# intertubeClock.net
KiCad netlist of a schematic drawn in EAGLE
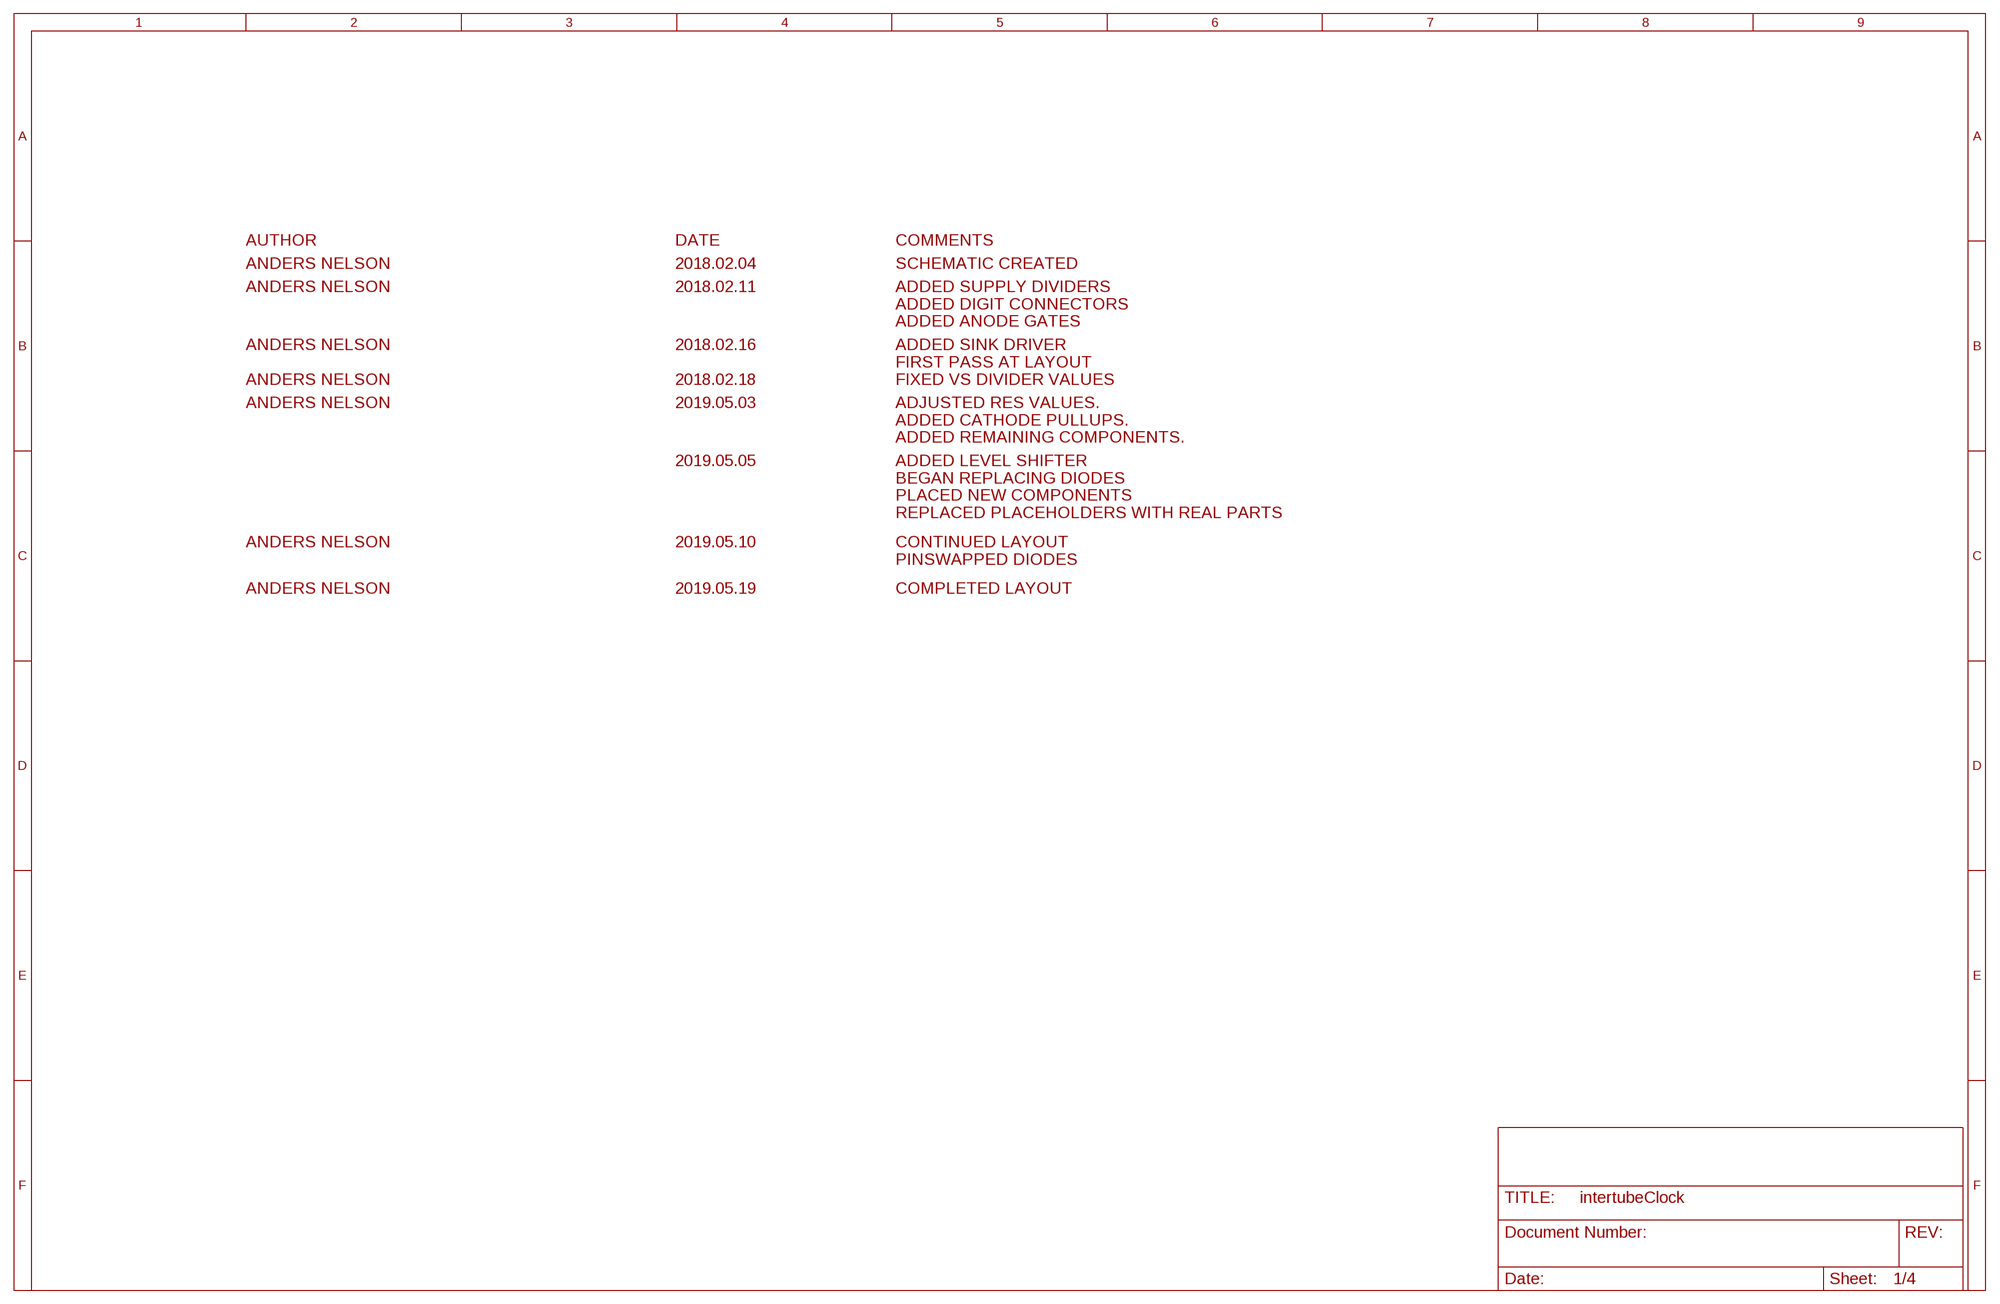
[diagram p0: schematic, sheet 1]
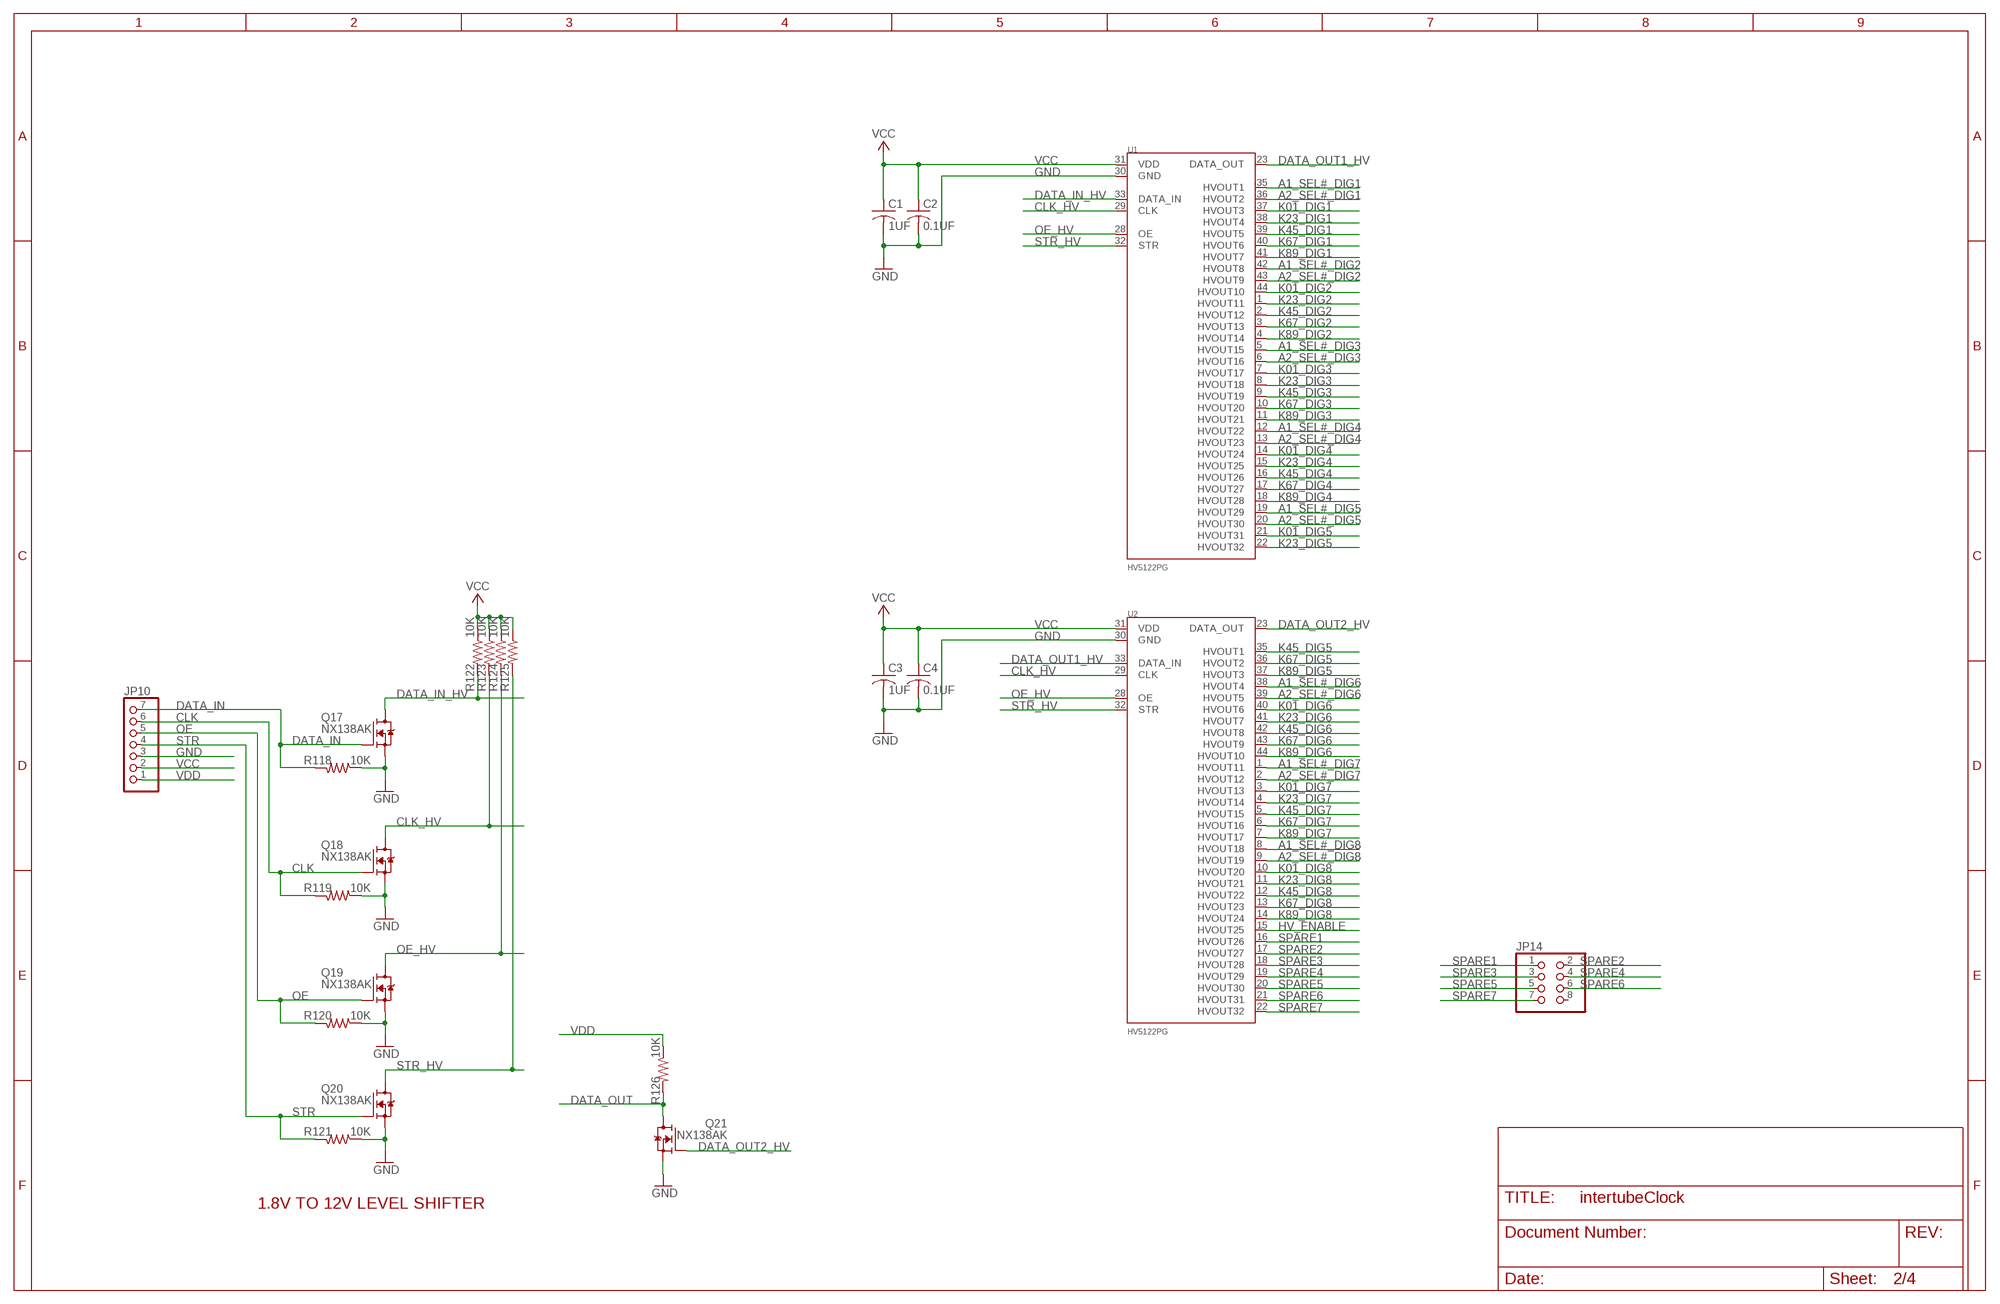
[diagram p1: schematic, sheet 2]
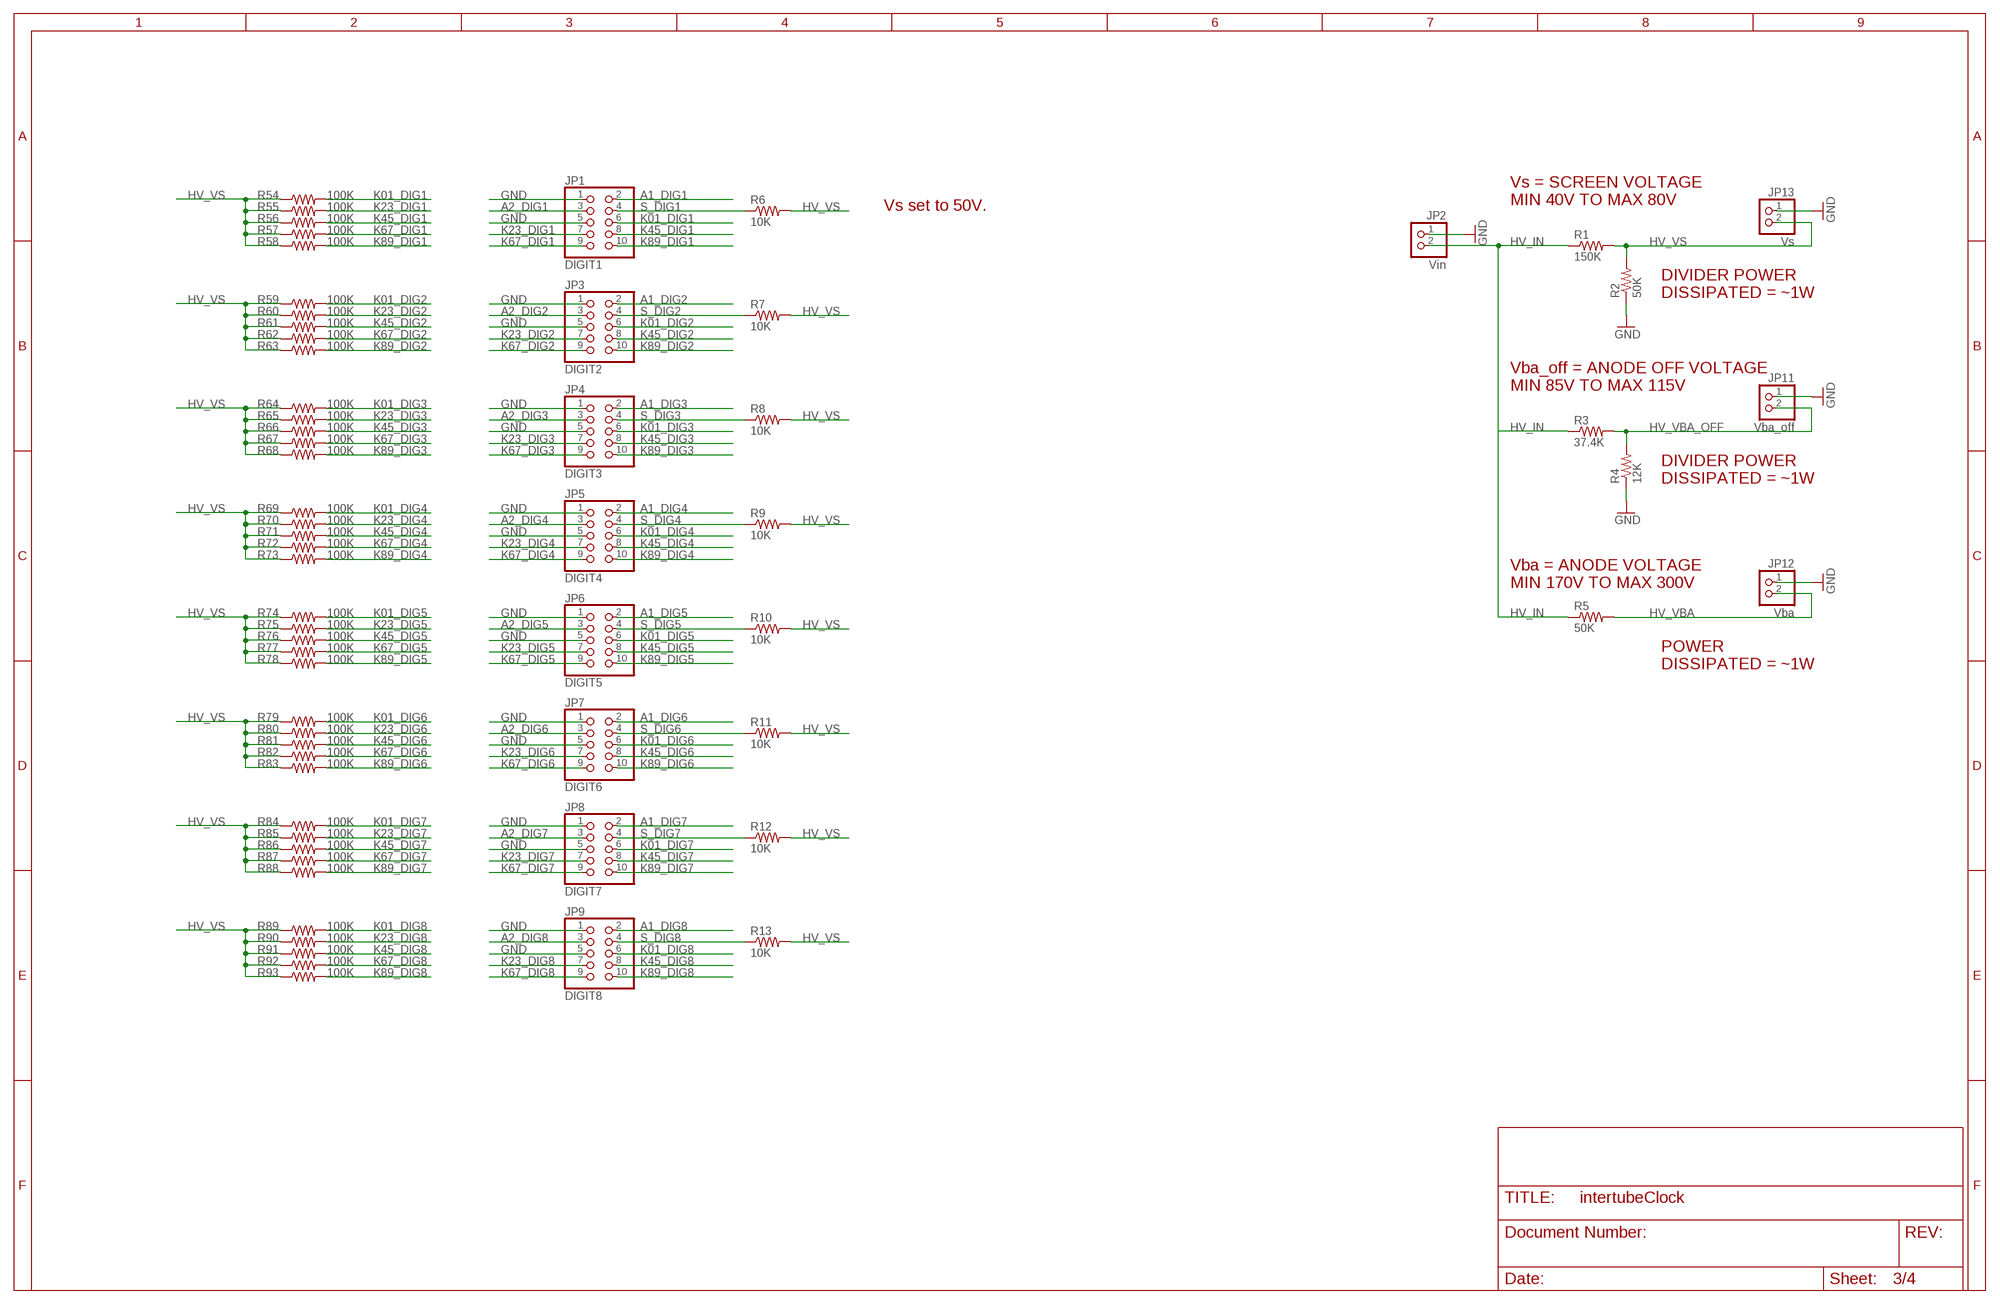
[diagram p2: schematic, sheet 3]
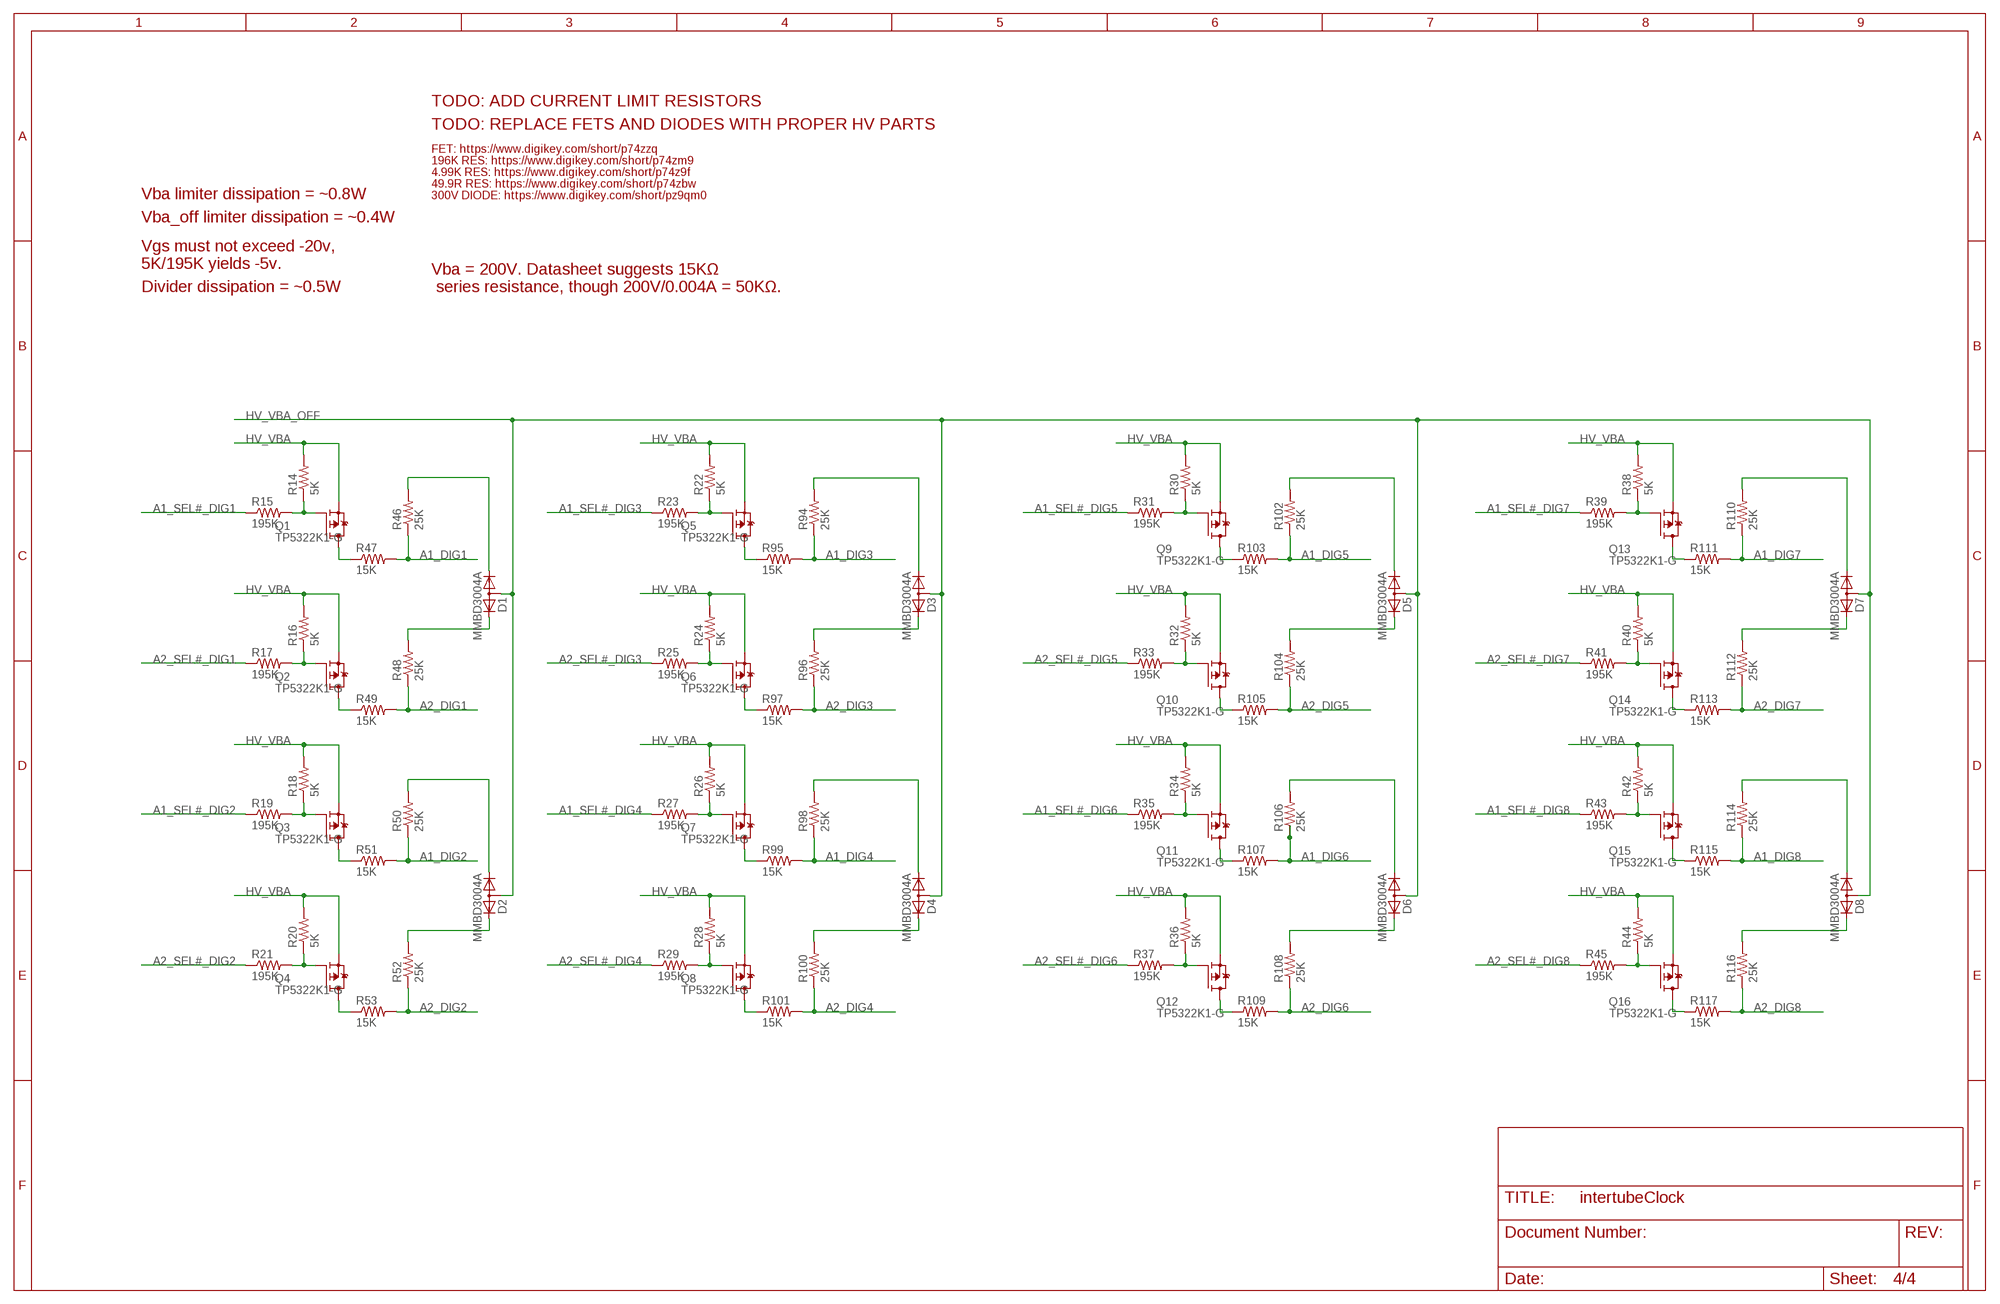
[diagram p3: schematic, sheet 4]

(export (version "E")
  (design (tool "Eeschema 10.0.6"))
  (components
    (comp (ref "JP1")
      (value "DIGIT1")
      (footprint "eagle-import:2X05")
      (libsource (lib "eagle-import") (part "PINHD-2X5"))
    )
    (comp (ref "JP2")
      (value "Vin")
      (footprint "eagle-import:1X02")
      (libsource (lib "eagle-import") (part "PINHD-1X2"))
    )
    (comp (ref "JP3")
      (value "DIGIT2")
      (footprint "eagle-import:2X05")
      (libsource (lib "eagle-import") (part "PINHD-2X5"))
    )
    (comp (ref "JP4")
      (value "DIGIT3")
      (footprint "eagle-import:2X05")
      (libsource (lib "eagle-import") (part "PINHD-2X5"))
    )
    (comp (ref "JP5")
      (value "DIGIT4")
      (footprint "eagle-import:2X05")
      (libsource (lib "eagle-import") (part "PINHD-2X5"))
    )
    (comp (ref "JP6")
      (value "DIGIT5")
      (footprint "eagle-import:2X05")
      (libsource (lib "eagle-import") (part "PINHD-2X5"))
    )
    (comp (ref "JP7")
      (value "DIGIT6")
      (footprint "eagle-import:2X05")
      (libsource (lib "eagle-import") (part "PINHD-2X5"))
    )
    (comp (ref "JP8")
      (value "DIGIT7")
      (footprint "eagle-import:2X05")
      (libsource (lib "eagle-import") (part "PINHD-2X5"))
    )
    (comp (ref "JP9")
      (value "DIGIT8")
      (footprint "eagle-import:2X05")
      (libsource (lib "eagle-import") (part "PINHD-2X5"))
    )
    (comp (ref "JP11")
      (value "Vba_off")
      (footprint "eagle-import:1X02")
      (libsource (lib "eagle-import") (part "PINHD-1X2"))
    )
    (comp (ref "JP12")
      (value "Vba")
      (footprint "eagle-import:1X02")
      (libsource (lib "eagle-import") (part "PINHD-1X2"))
    )
    (comp (ref "JP13")
      (value "Vs")
      (footprint "eagle-import:1X02")
      (libsource (lib "eagle-import") (part "PINHD-1X2"))
    )
    (comp (ref "R1")
      (value "150K")
      (footprint "eagle-import:R2512")
      (libsource (lib "eagle-import") (part "R-US_R2512"))
    )
    (comp (ref "R2")
      (value "50K")
      (footprint "eagle-import:R2512")
      (libsource (lib "eagle-import") (part "R-US_R2512"))
    )
    (comp (ref "R3")
      (value "37.4K")
      (footprint "eagle-import:R2512")
      (libsource (lib "eagle-import") (part "R-US_R2512"))
    )
    (comp (ref "R4")
      (value "12K")
      (footprint "eagle-import:R2512")
      (libsource (lib "eagle-import") (part "R-US_R2512"))
    )
    (comp (ref "R5")
      (value "50K")
      (footprint "eagle-import:R2512")
      (libsource (lib "eagle-import") (part "R-US_R2512"))
    )
    (comp (ref "R6")
      (value "10K")
      (footprint "eagle-import:R1206")
      (libsource (lib "eagle-import") (part "R-US_R1206"))
    )
    (comp (ref "R7")
      (value "10K")
      (footprint "eagle-import:R1206")
      (libsource (lib "eagle-import") (part "R-US_R1206"))
    )
    (comp (ref "R8")
      (value "10K")
      (footprint "eagle-import:R1206")
      (libsource (lib "eagle-import") (part "R-US_R1206"))
    )
    (comp (ref "R9")
      (value "10K")
      (footprint "eagle-import:R1206")
      (libsource (lib "eagle-import") (part "R-US_R1206"))
    )
    (comp (ref "R10")
      (value "10K")
      (footprint "eagle-import:R1206")
      (libsource (lib "eagle-import") (part "R-US_R1206"))
    )
    (comp (ref "R11")
      (value "10K")
      (footprint "eagle-import:R1206")
      (libsource (lib "eagle-import") (part "R-US_R1206"))
    )
    (comp (ref "R12")
      (value "10K")
      (footprint "eagle-import:R1206")
      (libsource (lib "eagle-import") (part "R-US_R1206"))
    )
    (comp (ref "R13")
      (value "10K")
      (footprint "eagle-import:R1206")
      (libsource (lib "eagle-import") (part "R-US_R1206"))
    )
    (comp (ref "R54")
      (value "100K")
      (footprint "eagle-import:R1206")
      (libsource (lib "eagle-import") (part "R-US_R1206"))
    )
    (comp (ref "R55")
      (value "100K")
      (footprint "eagle-import:R1206")
      (libsource (lib "eagle-import") (part "R-US_R1206"))
    )
    (comp (ref "R56")
      (value "100K")
      (footprint "eagle-import:R1206")
      (libsource (lib "eagle-import") (part "R-US_R1206"))
    )
    (comp (ref "R57")
      (value "100K")
      (footprint "eagle-import:R1206")
      (libsource (lib "eagle-import") (part "R-US_R1206"))
    )
    (comp (ref "R58")
      (value "100K")
      (footprint "eagle-import:R1206")
      (libsource (lib "eagle-import") (part "R-US_R1206"))
    )
    (comp (ref "R59")
      (value "100K")
      (footprint "eagle-import:R1206")
      (libsource (lib "eagle-import") (part "R-US_R1206"))
    )
    (comp (ref "R60")
      (value "100K")
      (footprint "eagle-import:R1206")
      (libsource (lib "eagle-import") (part "R-US_R1206"))
    )
    (comp (ref "R61")
      (value "100K")
      (footprint "eagle-import:R1206")
      (libsource (lib "eagle-import") (part "R-US_R1206"))
    )
    (comp (ref "R62")
      (value "100K")
      (footprint "eagle-import:R1206")
      (libsource (lib "eagle-import") (part "R-US_R1206"))
    )
    (comp (ref "R63")
      (value "100K")
      (footprint "eagle-import:R1206")
      (libsource (lib "eagle-import") (part "R-US_R1206"))
    )
    (comp (ref "R64")
      (value "100K")
      (footprint "eagle-import:R1206")
      (libsource (lib "eagle-import") (part "R-US_R1206"))
    )
    (comp (ref "R65")
      (value "100K")
      (footprint "eagle-import:R1206")
      (libsource (lib "eagle-import") (part "R-US_R1206"))
    )
    (comp (ref "R66")
      (value "100K")
      (footprint "eagle-import:R1206")
      (libsource (lib "eagle-import") (part "R-US_R1206"))
    )
    (comp (ref "R67")
      (value "100K")
      (footprint "eagle-import:R1206")
      (libsource (lib "eagle-import") (part "R-US_R1206"))
    )
    (comp (ref "R68")
      (value "100K")
      (footprint "eagle-import:R1206")
      (libsource (lib "eagle-import") (part "R-US_R1206"))
    )
    (comp (ref "R69")
      (value "100K")
      (footprint "eagle-import:R1206")
      (libsource (lib "eagle-import") (part "R-US_R1206"))
    )
    (comp (ref "R70")
      (value "100K")
      (footprint "eagle-import:R1206")
      (libsource (lib "eagle-import") (part "R-US_R1206"))
    )
    (comp (ref "R71")
      (value "100K")
      (footprint "eagle-import:R1206")
      (libsource (lib "eagle-import") (part "R-US_R1206"))
    )
    (comp (ref "R72")
      (value "100K")
      (footprint "eagle-import:R1206")
      (libsource (lib "eagle-import") (part "R-US_R1206"))
    )
    (comp (ref "R73")
      (value "100K")
      (footprint "eagle-import:R1206")
      (libsource (lib "eagle-import") (part "R-US_R1206"))
    )
    (comp (ref "R74")
      (value "100K")
      (footprint "eagle-import:R1206")
      (libsource (lib "eagle-import") (part "R-US_R1206"))
    )
    (comp (ref "R75")
      (value "100K")
      (footprint "eagle-import:R1206")
      (libsource (lib "eagle-import") (part "R-US_R1206"))
    )
    (comp (ref "R76")
      (value "100K")
      (footprint "eagle-import:R1206")
      (libsource (lib "eagle-import") (part "R-US_R1206"))
    )
    (comp (ref "R77")
      (value "100K")
      (footprint "eagle-import:R1206")
      (libsource (lib "eagle-import") (part "R-US_R1206"))
    )
    (comp (ref "R78")
      (value "100K")
      (footprint "eagle-import:R1206")
      (libsource (lib "eagle-import") (part "R-US_R1206"))
    )
    (comp (ref "R79")
      (value "100K")
      (footprint "eagle-import:R1206")
      (libsource (lib "eagle-import") (part "R-US_R1206"))
    )
    (comp (ref "R80")
      (value "100K")
      (footprint "eagle-import:R1206")
      (libsource (lib "eagle-import") (part "R-US_R1206"))
    )
    (comp (ref "R81")
      (value "100K")
      (footprint "eagle-import:R1206")
      (libsource (lib "eagle-import") (part "R-US_R1206"))
    )
    (comp (ref "R82")
      (value "100K")
      (footprint "eagle-import:R1206")
      (libsource (lib "eagle-import") (part "R-US_R1206"))
    )
    (comp (ref "R83")
      (value "100K")
      (footprint "eagle-import:R1206")
      (libsource (lib "eagle-import") (part "R-US_R1206"))
    )
    (comp (ref "R84")
      (value "100K")
      (footprint "eagle-import:R1206")
      (libsource (lib "eagle-import") (part "R-US_R1206"))
    )
    (comp (ref "R85")
      (value "100K")
      (footprint "eagle-import:R1206")
      (libsource (lib "eagle-import") (part "R-US_R1206"))
    )
    (comp (ref "R86")
      (value "100K")
      (footprint "eagle-import:R1206")
      (libsource (lib "eagle-import") (part "R-US_R1206"))
    )
    (comp (ref "R87")
      (value "100K")
      (footprint "eagle-import:R1206")
      (libsource (lib "eagle-import") (part "R-US_R1206"))
    )
    (comp (ref "R88")
      (value "100K")
      (footprint "eagle-import:R1206")
      (libsource (lib "eagle-import") (part "R-US_R1206"))
    )
    (comp (ref "R89")
      (value "100K")
      (footprint "eagle-import:R1206")
      (libsource (lib "eagle-import") (part "R-US_R1206"))
    )
    (comp (ref "R90")
      (value "100K")
      (footprint "eagle-import:R1206")
      (libsource (lib "eagle-import") (part "R-US_R1206"))
    )
    (comp (ref "R91")
      (value "100K")
      (footprint "eagle-import:R1206")
      (libsource (lib "eagle-import") (part "R-US_R1206"))
    )
    (comp (ref "R92")
      (value "100K")
      (footprint "eagle-import:R1206")
      (libsource (lib "eagle-import") (part "R-US_R1206"))
    )
    (comp (ref "R93")
      (value "100K")
      (footprint "eagle-import:R1206")
      (libsource (lib "eagle-import") (part "R-US_R1206"))
    )
    (comp (ref "D1")
      (value "MMBD3004A")
      (footprint "eagle-import:SOT23")
      (libsource (lib "eagle-import") (part "MMBD3004A"))
    )
    (comp (ref "D2")
      (value "MMBD3004A")
      (footprint "eagle-import:SOT23")
      (libsource (lib "eagle-import") (part "MMBD3004A"))
    )
    (comp (ref "D3")
      (value "MMBD3004A")
      (footprint "eagle-import:SOT23")
      (libsource (lib "eagle-import") (part "MMBD3004A"))
    )
    (comp (ref "D4")
      (value "MMBD3004A")
      (footprint "eagle-import:SOT23")
      (libsource (lib "eagle-import") (part "MMBD3004A"))
    )
    (comp (ref "D5")
      (value "MMBD3004A")
      (footprint "eagle-import:SOT23")
      (libsource (lib "eagle-import") (part "MMBD3004A"))
    )
    (comp (ref "D6")
      (value "MMBD3004A")
      (footprint "eagle-import:SOT23")
      (libsource (lib "eagle-import") (part "MMBD3004A"))
    )
    (comp (ref "D7")
      (value "MMBD3004A")
      (footprint "eagle-import:SOT23")
      (libsource (lib "eagle-import") (part "MMBD3004A"))
    )
    (comp (ref "D8")
      (value "MMBD3004A")
      (footprint "eagle-import:SOT23")
      (libsource (lib "eagle-import") (part "MMBD3004A"))
    )
    (comp (ref "Q1")
      (value "TP5322K1-G")
      (footprint "eagle-import:SOT23")
      (libsource (lib "eagle-import") (part "TP5322K1-G"))
    )
    (comp (ref "Q2")
      (value "TP5322K1-G")
      (footprint "eagle-import:SOT23")
      (libsource (lib "eagle-import") (part "TP5322K1-G"))
    )
    (comp (ref "Q3")
      (value "TP5322K1-G")
      (footprint "eagle-import:SOT23")
      (libsource (lib "eagle-import") (part "TP5322K1-G"))
    )
    (comp (ref "Q4")
      (value "TP5322K1-G")
      (footprint "eagle-import:SOT23")
      (libsource (lib "eagle-import") (part "TP5322K1-G"))
    )
    (comp (ref "Q5")
      (value "TP5322K1-G")
      (footprint "eagle-import:SOT23")
      (libsource (lib "eagle-import") (part "TP5322K1-G"))
    )
    (comp (ref "Q6")
      (value "TP5322K1-G")
      (footprint "eagle-import:SOT23")
      (libsource (lib "eagle-import") (part "TP5322K1-G"))
    )
    (comp (ref "Q7")
      (value "TP5322K1-G")
      (footprint "eagle-import:SOT23")
      (libsource (lib "eagle-import") (part "TP5322K1-G"))
    )
    (comp (ref "Q8")
      (value "TP5322K1-G")
      (footprint "eagle-import:SOT23")
      (libsource (lib "eagle-import") (part "TP5322K1-G"))
    )
    (comp (ref "Q9")
      (value "TP5322K1-G")
      (footprint "eagle-import:SOT23")
      (libsource (lib "eagle-import") (part "TP5322K1-G"))
    )
    (comp (ref "Q10")
      (value "TP5322K1-G")
      (footprint "eagle-import:SOT23")
      (libsource (lib "eagle-import") (part "TP5322K1-G"))
    )
    (comp (ref "Q11")
      (value "TP5322K1-G")
      (footprint "eagle-import:SOT23")
      (libsource (lib "eagle-import") (part "TP5322K1-G"))
    )
    (comp (ref "Q12")
      (value "TP5322K1-G")
      (footprint "eagle-import:SOT23")
      (libsource (lib "eagle-import") (part "TP5322K1-G"))
    )
    (comp (ref "Q13")
      (value "TP5322K1-G")
      (footprint "eagle-import:SOT23")
      (libsource (lib "eagle-import") (part "TP5322K1-G"))
    )
    (comp (ref "Q14")
      (value "TP5322K1-G")
      (footprint "eagle-import:SOT23")
      (libsource (lib "eagle-import") (part "TP5322K1-G"))
    )
    (comp (ref "Q15")
      (value "TP5322K1-G")
      (footprint "eagle-import:SOT23")
      (libsource (lib "eagle-import") (part "TP5322K1-G"))
    )
    (comp (ref "Q16")
      (value "TP5322K1-G")
      (footprint "eagle-import:SOT23")
      (libsource (lib "eagle-import") (part "TP5322K1-G"))
    )
    (comp (ref "R14")
      (value "5K")
      (footprint "eagle-import:R1206")
      (libsource (lib "eagle-import") (part "R-US_R1206"))
    )
    (comp (ref "R15")
      (value "195K")
      (footprint "eagle-import:R1206")
      (libsource (lib "eagle-import") (part "R-US_R1206"))
    )
    (comp (ref "R16")
      (value "5K")
      (footprint "eagle-import:R1206")
      (libsource (lib "eagle-import") (part "R-US_R1206"))
    )
    (comp (ref "R17")
      (value "195K")
      (footprint "eagle-import:R1206")
      (libsource (lib "eagle-import") (part "R-US_R1206"))
    )
    (comp (ref "R18")
      (value "5K")
      (footprint "eagle-import:R1206")
      (libsource (lib "eagle-import") (part "R-US_R1206"))
    )
    (comp (ref "R19")
      (value "195K")
      (footprint "eagle-import:R1206")
      (libsource (lib "eagle-import") (part "R-US_R1206"))
    )
    (comp (ref "R20")
      (value "5K")
      (footprint "eagle-import:R1206")
      (libsource (lib "eagle-import") (part "R-US_R1206"))
    )
    (comp (ref "R21")
      (value "195K")
      (footprint "eagle-import:R1206")
      (libsource (lib "eagle-import") (part "R-US_R1206"))
    )
    (comp (ref "R22")
      (value "5K")
      (footprint "eagle-import:R1206")
      (libsource (lib "eagle-import") (part "R-US_R1206"))
    )
    (comp (ref "R23")
      (value "195K")
      (footprint "eagle-import:R1206")
      (libsource (lib "eagle-import") (part "R-US_R1206"))
    )
    (comp (ref "R24")
      (value "5K")
      (footprint "eagle-import:R1206")
      (libsource (lib "eagle-import") (part "R-US_R1206"))
    )
    (comp (ref "R25")
      (value "195K")
      (footprint "eagle-import:R1206")
      (libsource (lib "eagle-import") (part "R-US_R1206"))
    )
    (comp (ref "R26")
      (value "5K")
      (footprint "eagle-import:R1206")
      (libsource (lib "eagle-import") (part "R-US_R1206"))
    )
    (comp (ref "R27")
      (value "195K")
      (footprint "eagle-import:R1206")
      (libsource (lib "eagle-import") (part "R-US_R1206"))
    )
    (comp (ref "R28")
      (value "5K")
      (footprint "eagle-import:R1206")
      (libsource (lib "eagle-import") (part "R-US_R1206"))
    )
    (comp (ref "R29")
      (value "195K")
      (footprint "eagle-import:R1206")
      (libsource (lib "eagle-import") (part "R-US_R1206"))
    )
    (comp (ref "R30")
      (value "5K")
      (footprint "eagle-import:R1206")
      (libsource (lib "eagle-import") (part "R-US_R1206"))
    )
    (comp (ref "R31")
      (value "195K")
      (footprint "eagle-import:R1206")
      (libsource (lib "eagle-import") (part "R-US_R1206"))
    )
    (comp (ref "R32")
      (value "5K")
      (footprint "eagle-import:R1206")
      (libsource (lib "eagle-import") (part "R-US_R1206"))
    )
    (comp (ref "R33")
      (value "195K")
      (footprint "eagle-import:R1206")
      (libsource (lib "eagle-import") (part "R-US_R1206"))
    )
    (comp (ref "R34")
      (value "5K")
      (footprint "eagle-import:R1206")
      (libsource (lib "eagle-import") (part "R-US_R1206"))
    )
    (comp (ref "R35")
      (value "195K")
      (footprint "eagle-import:R1206")
      (libsource (lib "eagle-import") (part "R-US_R1206"))
    )
    (comp (ref "R36")
      (value "5K")
      (footprint "eagle-import:R1206")
      (libsource (lib "eagle-import") (part "R-US_R1206"))
    )
    (comp (ref "R37")
      (value "195K")
      (footprint "eagle-import:R1206")
      (libsource (lib "eagle-import") (part "R-US_R1206"))
    )
    (comp (ref "R38")
      (value "5K")
      (footprint "eagle-import:R1206")
      (libsource (lib "eagle-import") (part "R-US_R1206"))
    )
    (comp (ref "R39")
      (value "195K")
      (footprint "eagle-import:R1206")
      (libsource (lib "eagle-import") (part "R-US_R1206"))
    )
    (comp (ref "R40")
      (value "5K")
      (footprint "eagle-import:R1206")
      (libsource (lib "eagle-import") (part "R-US_R1206"))
    )
    (comp (ref "R41")
      (value "195K")
      (footprint "eagle-import:R1206")
      (libsource (lib "eagle-import") (part "R-US_R1206"))
    )
    (comp (ref "R42")
      (value "5K")
      (footprint "eagle-import:R1206")
      (libsource (lib "eagle-import") (part "R-US_R1206"))
    )
    (comp (ref "R43")
      (value "195K")
      (footprint "eagle-import:R1206")
      (libsource (lib "eagle-import") (part "R-US_R1206"))
    )
    (comp (ref "R44")
      (value "5K")
      (footprint "eagle-import:R1206")
      (libsource (lib "eagle-import") (part "R-US_R1206"))
    )
    (comp (ref "R45")
      (value "195K")
      (footprint "eagle-import:R1206")
      (libsource (lib "eagle-import") (part "R-US_R1206"))
    )
    (comp (ref "R46")
      (value "25K")
      (footprint "eagle-import:R1206")
      (libsource (lib "eagle-import") (part "R-US_R1206"))
    )
    (comp (ref "R47")
      (value "15K")
      (footprint "eagle-import:R1206")
      (libsource (lib "eagle-import") (part "R-US_R1206"))
    )
    (comp (ref "R48")
      (value "25K")
      (footprint "eagle-import:R1206")
      (libsource (lib "eagle-import") (part "R-US_R1206"))
    )
    (comp (ref "R49")
      (value "15K")
      (footprint "eagle-import:R1206")
      (libsource (lib "eagle-import") (part "R-US_R1206"))
    )
    (comp (ref "R50")
      (value "25K")
      (footprint "eagle-import:R1206")
      (libsource (lib "eagle-import") (part "R-US_R1206"))
    )
    (comp (ref "R51")
      (value "15K")
      (footprint "eagle-import:R1206")
      (libsource (lib "eagle-import") (part "R-US_R1206"))
    )
    (comp (ref "R52")
      (value "25K")
      (footprint "eagle-import:R1206")
      (libsource (lib "eagle-import") (part "R-US_R1206"))
    )
    (comp (ref "R53")
      (value "15K")
      (footprint "eagle-import:R1206")
      (libsource (lib "eagle-import") (part "R-US_R1206"))
    )
    (comp (ref "R94")
      (value "25K")
      (footprint "eagle-import:R1206")
      (libsource (lib "eagle-import") (part "R-US_R1206"))
    )
    (comp (ref "R95")
      (value "15K")
      (footprint "eagle-import:R1206")
      (libsource (lib "eagle-import") (part "R-US_R1206"))
    )
    (comp (ref "R96")
      (value "25K")
      (footprint "eagle-import:R1206")
      (libsource (lib "eagle-import") (part "R-US_R1206"))
    )
    (comp (ref "R97")
      (value "15K")
      (footprint "eagle-import:R1206")
      (libsource (lib "eagle-import") (part "R-US_R1206"))
    )
    (comp (ref "R98")
      (value "25K")
      (footprint "eagle-import:R1206")
      (libsource (lib "eagle-import") (part "R-US_R1206"))
    )
    (comp (ref "R99")
      (value "15K")
      (footprint "eagle-import:R1206")
      (libsource (lib "eagle-import") (part "R-US_R1206"))
    )
    (comp (ref "R100")
      (value "25K")
      (footprint "eagle-import:R1206")
      (libsource (lib "eagle-import") (part "R-US_R1206"))
    )
    (comp (ref "R101")
      (value "15K")
      (footprint "eagle-import:R1206")
      (libsource (lib "eagle-import") (part "R-US_R1206"))
    )
    (comp (ref "R102")
      (value "25K")
      (footprint "eagle-import:R1206")
      (libsource (lib "eagle-import") (part "R-US_R1206"))
    )
    (comp (ref "R103")
      (value "15K")
      (footprint "eagle-import:R1206")
      (libsource (lib "eagle-import") (part "R-US_R1206"))
    )
    (comp (ref "R104")
      (value "25K")
      (footprint "eagle-import:R1206")
      (libsource (lib "eagle-import") (part "R-US_R1206"))
    )
    (comp (ref "R105")
      (value "15K")
      (footprint "eagle-import:R1206")
      (libsource (lib "eagle-import") (part "R-US_R1206"))
    )
    (comp (ref "R106")
      (value "25K")
      (footprint "eagle-import:R1206")
      (libsource (lib "eagle-import") (part "R-US_R1206"))
    )
    (comp (ref "R107")
      (value "15K")
      (footprint "eagle-import:R1206")
      (libsource (lib "eagle-import") (part "R-US_R1206"))
    )
    (comp (ref "R108")
      (value "25K")
      (footprint "eagle-import:R1206")
      (libsource (lib "eagle-import") (part "R-US_R1206"))
    )
    (comp (ref "R109")
      (value "15K")
      (footprint "eagle-import:R1206")
      (libsource (lib "eagle-import") (part "R-US_R1206"))
    )
    (comp (ref "R110")
      (value "25K")
      (footprint "eagle-import:R1206")
      (libsource (lib "eagle-import") (part "R-US_R1206"))
    )
    (comp (ref "R111")
      (value "15K")
      (footprint "eagle-import:R1206")
      (libsource (lib "eagle-import") (part "R-US_R1206"))
    )
    (comp (ref "R112")
      (value "25K")
      (footprint "eagle-import:R1206")
      (libsource (lib "eagle-import") (part "R-US_R1206"))
    )
    (comp (ref "R113")
      (value "15K")
      (footprint "eagle-import:R1206")
      (libsource (lib "eagle-import") (part "R-US_R1206"))
    )
    (comp (ref "R114")
      (value "25K")
      (footprint "eagle-import:R1206")
      (libsource (lib "eagle-import") (part "R-US_R1206"))
    )
    (comp (ref "R115")
      (value "15K")
      (footprint "eagle-import:R1206")
      (libsource (lib "eagle-import") (part "R-US_R1206"))
    )
    (comp (ref "R116")
      (value "25K")
      (footprint "eagle-import:R1206")
      (libsource (lib "eagle-import") (part "R-US_R1206"))
    )
    (comp (ref "R117")
      (value "15K")
      (footprint "eagle-import:R1206")
      (libsource (lib "eagle-import") (part "R-US_R1206"))
    )
    (comp (ref "C1")
      (value "1UF")
      (footprint "eagle-import:C0805")
      (libsource (lib "eagle-import") (part "C-USC0805"))
    )
    (comp (ref "C2")
      (value "0.1UF")
      (footprint "eagle-import:C0805")
      (libsource (lib "eagle-import") (part "C-USC0805"))
    )
    (comp (ref "C3")
      (value "1UF")
      (footprint "eagle-import:C0805")
      (libsource (lib "eagle-import") (part "C-USC0805"))
    )
    (comp (ref "C4")
      (value "0.1UF")
      (footprint "eagle-import:C0805")
      (libsource (lib "eagle-import") (part "C-USC0805"))
    )
    (comp (ref "JP10")
      (value "PINHD-1X7")
      (footprint "eagle-import:1X07")
      (libsource (lib "eagle-import") (part "PINHD-1X7"))
    )
    (comp (ref "JP14")
      (value "PINHD-2X4")
      (footprint "eagle-import:2X04")
      (libsource (lib "eagle-import") (part "PINHD-2X4"))
    )
    (comp (ref "Q17")
      (value "NX138AK")
      (footprint "eagle-import:SOT23")
      (libsource (lib "eagle-import") (part "NX138AK"))
    )
    (comp (ref "Q18")
      (value "NX138AK")
      (footprint "eagle-import:SOT23")
      (libsource (lib "eagle-import") (part "NX138AK"))
    )
    (comp (ref "Q19")
      (value "NX138AK")
      (footprint "eagle-import:SOT23")
      (libsource (lib "eagle-import") (part "NX138AK"))
    )
    (comp (ref "Q20")
      (value "NX138AK")
      (footprint "eagle-import:SOT23")
      (libsource (lib "eagle-import") (part "NX138AK"))
    )
    (comp (ref "Q21")
      (value "NX138AK")
      (footprint "eagle-import:SOT23")
      (libsource (lib "eagle-import") (part "NX138AK"))
    )
    (comp (ref "R118")
      (value "10K")
      (footprint "eagle-import:R0603")
      (libsource (lib "eagle-import") (part "R-US_R0603"))
    )
    (comp (ref "R119")
      (value "10K")
      (footprint "eagle-import:R0603")
      (libsource (lib "eagle-import") (part "R-US_R0603"))
    )
    (comp (ref "R120")
      (value "10K")
      (footprint "eagle-import:R0603")
      (libsource (lib "eagle-import") (part "R-US_R0603"))
    )
    (comp (ref "R121")
      (value "10K")
      (footprint "eagle-import:R0603")
      (libsource (lib "eagle-import") (part "R-US_R0603"))
    )
    (comp (ref "R122")
      (value "10K")
      (footprint "eagle-import:R0603")
      (libsource (lib "eagle-import") (part "R-US_R0603"))
    )
    (comp (ref "R123")
      (value "10K")
      (footprint "eagle-import:R0603")
      (libsource (lib "eagle-import") (part "R-US_R0603"))
    )
    (comp (ref "R124")
      (value "10K")
      (footprint "eagle-import:R0603")
      (libsource (lib "eagle-import") (part "R-US_R0603"))
    )
    (comp (ref "R125")
      (value "10K")
      (footprint "eagle-import:R0603")
      (libsource (lib "eagle-import") (part "R-US_R0603"))
    )
    (comp (ref "R126")
      (value "10K")
      (footprint "eagle-import:R0603")
      (libsource (lib "eagle-import") (part "R-US_R0603"))
    )
    (comp (ref "U1")
      (value "HV5122PG")
      (footprint "eagle-import:TQFP44")
      (libsource (lib "eagle-import") (part "HV5PG122"))
    )
    (comp (ref "U2")
      (value "HV5122PG")
      (footprint "eagle-import:TQFP44")
      (libsource (lib "eagle-import") (part "HV5PG122"))
    )
  )
  (nets
    (net (code "1") (name "A1_DIG1") (class "Default")
      (node (ref "JP1") (pin "2") (pinfunction "2_2") (pintype "passive"))
      (node (ref "R46") (pin "1") (pinfunction "1_1") (pintype "passive"))
      (node (ref "R47") (pin "2") (pinfunction "2_2") (pintype "passive"))
    )
    (net (code "2") (name "A1_DIG2") (class "Default")
      (node (ref "JP3") (pin "2") (pinfunction "2_2") (pintype "passive"))
      (node (ref "R50") (pin "1") (pinfunction "1_1") (pintype "passive"))
      (node (ref "R51") (pin "2") (pinfunction "2_2") (pintype "passive"))
    )
    (net (code "3") (name "A1_DIG3") (class "Default")
      (node (ref "JP4") (pin "2") (pinfunction "2_2") (pintype "passive"))
      (node (ref "R94") (pin "1") (pinfunction "1_1") (pintype "passive"))
      (node (ref "R95") (pin "2") (pinfunction "2_2") (pintype "passive"))
    )
    (net (code "4") (name "A1_DIG4") (class "Default")
      (node (ref "JP5") (pin "2") (pinfunction "2_2") (pintype "passive"))
      (node (ref "R98") (pin "1") (pinfunction "1_1") (pintype "passive"))
      (node (ref "R99") (pin "2") (pinfunction "2_2") (pintype "passive"))
    )
    (net (code "5") (name "A1_DIG5") (class "Default")
      (node (ref "JP6") (pin "2") (pinfunction "2_2") (pintype "passive"))
      (node (ref "R102") (pin "1") (pinfunction "1_1") (pintype "passive"))
      (node (ref "R103") (pin "2") (pinfunction "2_2") (pintype "passive"))
    )
    (net (code "6") (name "A1_DIG6") (class "Default")
      (node (ref "JP7") (pin "2") (pinfunction "2_2") (pintype "passive"))
      (node (ref "R106") (pin "1") (pinfunction "1_1") (pintype "passive"))
      (node (ref "R107") (pin "2") (pinfunction "2_2") (pintype "passive"))
    )
    (net (code "7") (name "A1_DIG7") (class "Default")
      (node (ref "JP8") (pin "2") (pinfunction "2_2") (pintype "passive"))
      (node (ref "R110") (pin "1") (pinfunction "1_1") (pintype "passive"))
      (node (ref "R111") (pin "2") (pinfunction "2_2") (pintype "passive"))
    )
    (net (code "8") (name "A1_DIG8") (class "Default")
      (node (ref "JP9") (pin "2") (pinfunction "2_2") (pintype "passive"))
      (node (ref "R114") (pin "1") (pinfunction "1_1") (pintype "passive"))
      (node (ref "R115") (pin "2") (pinfunction "2_2") (pintype "passive"))
    )
    (net (code "9") (name "A1_SEL#_DIG1") (class "Default")
      (node (ref "R15") (pin "1") (pinfunction "1_1") (pintype "passive"))
      (node (ref "U1") (pin "35") (pinfunction "HVOUT1_35") (pintype "bidirectional"))
    )
    (net (code "10") (name "A1_SEL#_DIG2") (class "Default")
      (node (ref "R19") (pin "1") (pinfunction "1_1") (pintype "passive"))
      (node (ref "U1") (pin "42") (pinfunction "HVOUT8_42") (pintype "bidirectional"))
    )
    (net (code "11") (name "A1_SEL#_DIG3") (class "Default")
      (node (ref "R23") (pin "1") (pinfunction "1_1") (pintype "passive"))
      (node (ref "U1") (pin "5") (pinfunction "HVOUT15_5") (pintype "bidirectional"))
    )
    (net (code "12") (name "A1_SEL#_DIG4") (class "Default")
      (node (ref "R27") (pin "1") (pinfunction "1_1") (pintype "passive"))
      (node (ref "U1") (pin "12") (pinfunction "HVOUT22_12") (pintype "bidirectional"))
    )
    (net (code "13") (name "A1_SEL#_DIG5") (class "Default")
      (node (ref "R31") (pin "1") (pinfunction "1_1") (pintype "passive"))
      (node (ref "U1") (pin "19") (pinfunction "HVOUT29_19") (pintype "bidirectional"))
    )
    (net (code "14") (name "A1_SEL#_DIG6") (class "Default")
      (node (ref "R35") (pin "1") (pinfunction "1_1") (pintype "passive"))
      (node (ref "U2") (pin "38") (pinfunction "HVOUT4_38") (pintype "bidirectional"))
    )
    (net (code "15") (name "A1_SEL#_DIG7") (class "Default")
      (node (ref "R39") (pin "1") (pinfunction "1_1") (pintype "passive"))
      (node (ref "U2") (pin "1") (pinfunction "HVOUT11_1") (pintype "bidirectional"))
    )
    (net (code "16") (name "A1_SEL#_DIG8") (class "Default")
      (node (ref "R43") (pin "1") (pinfunction "1_1") (pintype "passive"))
      (node (ref "U2") (pin "8") (pinfunction "HVOUT18_8") (pintype "bidirectional"))
    )
    (net (code "17") (name "A2_DIG1") (class "Default")
      (node (ref "JP1") (pin "3") (pinfunction "3_3") (pintype "passive"))
      (node (ref "R48") (pin "1") (pinfunction "1_1") (pintype "passive"))
      (node (ref "R49") (pin "2") (pinfunction "2_2") (pintype "passive"))
    )
    (net (code "18") (name "A2_DIG2") (class "Default")
      (node (ref "JP3") (pin "3") (pinfunction "3_3") (pintype "passive"))
      (node (ref "R52") (pin "1") (pinfunction "1_1") (pintype "passive"))
      (node (ref "R53") (pin "2") (pinfunction "2_2") (pintype "passive"))
    )
    (net (code "19") (name "A2_DIG3") (class "Default")
      (node (ref "JP4") (pin "3") (pinfunction "3_3") (pintype "passive"))
      (node (ref "R96") (pin "1") (pinfunction "1_1") (pintype "passive"))
      (node (ref "R97") (pin "2") (pinfunction "2_2") (pintype "passive"))
    )
    (net (code "20") (name "A2_DIG4") (class "Default")
      (node (ref "JP5") (pin "3") (pinfunction "3_3") (pintype "passive"))
      (node (ref "R100") (pin "1") (pinfunction "1_1") (pintype "passive"))
      (node (ref "R101") (pin "2") (pinfunction "2_2") (pintype "passive"))
    )
    (net (code "21") (name "A2_DIG5") (class "Default")
      (node (ref "JP6") (pin "3") (pinfunction "3_3") (pintype "passive"))
      (node (ref "R104") (pin "1") (pinfunction "1_1") (pintype "passive"))
      (node (ref "R105") (pin "2") (pinfunction "2_2") (pintype "passive"))
    )
    (net (code "22") (name "A2_DIG6") (class "Default")
      (node (ref "JP7") (pin "3") (pinfunction "3_3") (pintype "passive"))
      (node (ref "R108") (pin "1") (pinfunction "1_1") (pintype "passive"))
      (node (ref "R109") (pin "2") (pinfunction "2_2") (pintype "passive"))
    )
    (net (code "23") (name "A2_DIG7") (class "Default")
      (node (ref "JP8") (pin "3") (pinfunction "3_3") (pintype "passive"))
      (node (ref "R112") (pin "1") (pinfunction "1_1") (pintype "passive"))
      (node (ref "R113") (pin "2") (pinfunction "2_2") (pintype "passive"))
    )
    (net (code "24") (name "A2_DIG8") (class "Default")
      (node (ref "JP9") (pin "3") (pinfunction "3_3") (pintype "passive"))
      (node (ref "R116") (pin "1") (pinfunction "1_1") (pintype "passive"))
      (node (ref "R117") (pin "2") (pinfunction "2_2") (pintype "passive"))
    )
    (net (code "25") (name "A2_SEL#_DIG1") (class "Default")
      (node (ref "R17") (pin "1") (pinfunction "1_1") (pintype "passive"))
      (node (ref "U1") (pin "36") (pinfunction "HVOUT2_36") (pintype "bidirectional"))
    )
    (net (code "26") (name "A2_SEL#_DIG2") (class "Default")
      (node (ref "R21") (pin "1") (pinfunction "1_1") (pintype "passive"))
      (node (ref "U1") (pin "43") (pinfunction "HVOUT9_43") (pintype "bidirectional"))
    )
    (net (code "27") (name "A2_SEL#_DIG3") (class "Default")
      (node (ref "R25") (pin "1") (pinfunction "1_1") (pintype "passive"))
      (node (ref "U1") (pin "6") (pinfunction "HVOUT16_6") (pintype "bidirectional"))
    )
    (net (code "28") (name "A2_SEL#_DIG4") (class "Default")
      (node (ref "R29") (pin "1") (pinfunction "1_1") (pintype "passive"))
      (node (ref "U1") (pin "13") (pinfunction "HVOUT23_13") (pintype "bidirectional"))
    )
    (net (code "29") (name "A2_SEL#_DIG5") (class "Default")
      (node (ref "R33") (pin "1") (pinfunction "1_1") (pintype "passive"))
      (node (ref "U1") (pin "20") (pinfunction "HVOUT30_20") (pintype "bidirectional"))
    )
    (net (code "30") (name "A2_SEL#_DIG6") (class "Default")
      (node (ref "R37") (pin "1") (pinfunction "1_1") (pintype "passive"))
      (node (ref "U2") (pin "39") (pinfunction "HVOUT5_39") (pintype "bidirectional"))
    )
    (net (code "31") (name "A2_SEL#_DIG7") (class "Default")
      (node (ref "R41") (pin "1") (pinfunction "1_1") (pintype "passive"))
      (node (ref "U2") (pin "2") (pinfunction "HVOUT12_2") (pintype "bidirectional"))
    )
    (net (code "32") (name "A2_SEL#_DIG8") (class "Default")
      (node (ref "R45") (pin "1") (pinfunction "1_1") (pintype "passive"))
      (node (ref "U2") (pin "9") (pinfunction "HVOUT19_9") (pintype "bidirectional"))
    )
    (net (code "33") (name "CLK") (class "Default")
      (node (ref "JP10") (pin "6") (pinfunction "6_6") (pintype "passive"))
      (node (ref "Q18") (pin "1") (pinfunction "G_1") (pintype "passive"))
      (node (ref "R119") (pin "2") (pinfunction "2_2") (pintype "passive"))
    )
    (net (code "34") (name "CLK_HV") (class "Default")
      (node (ref "Q18") (pin "3") (pinfunction "D_3") (pintype "passive"))
      (node (ref "R123") (pin "2") (pinfunction "2_2") (pintype "passive"))
      (node (ref "U1") (pin "29") (pinfunction "CLK_29") (pintype "bidirectional"))
      (node (ref "U2") (pin "29") (pinfunction "CLK_29") (pintype "bidirectional"))
    )
    (net (code "35") (name "DATA_IN") (class "Default")
      (node (ref "JP10") (pin "7") (pinfunction "7_7") (pintype "passive"))
      (node (ref "Q17") (pin "1") (pinfunction "G_1") (pintype "passive"))
      (node (ref "R118") (pin "2") (pinfunction "2_2") (pintype "passive"))
    )
    (net (code "36") (name "DATA_IN_HV") (class "Default")
      (node (ref "Q17") (pin "3") (pinfunction "D_3") (pintype "passive"))
      (node (ref "R122") (pin "2") (pinfunction "2_2") (pintype "passive"))
      (node (ref "U1") (pin "33") (pinfunction "DATA_IN_33") (pintype "bidirectional"))
    )
    (net (code "37") (name "DATA_OUT") (class "Default")
      (node (ref "Q21") (pin "3") (pinfunction "D_3") (pintype "passive"))
      (node (ref "R126") (pin "2") (pinfunction "2_2") (pintype "passive"))
    )
    (net (code "38") (name "DATA_OUT1_HV") (class "Default")
      (node (ref "U1") (pin "23") (pinfunction "DATA_OUT_23") (pintype "bidirectional"))
      (node (ref "U2") (pin "33") (pinfunction "DATA_IN_33") (pintype "bidirectional"))
    )
    (net (code "39") (name "DATA_OUT2_HV") (class "Default")
      (node (ref "Q21") (pin "1") (pinfunction "G_1") (pintype "passive"))
      (node (ref "U2") (pin "23") (pinfunction "DATA_OUT_23") (pintype "bidirectional"))
    )
    (net (code "40") (name "GND") (class "Default")
      (node (ref "C1") (pin "2") (pinfunction "2_2") (pintype "passive"))
      (node (ref "C2") (pin "2") (pinfunction "2_2") (pintype "passive"))
      (node (ref "C3") (pin "2") (pinfunction "2_2") (pintype "passive"))
      (node (ref "C4") (pin "2") (pinfunction "2_2") (pintype "passive"))
      (node (ref "JP1") (pin "1") (pinfunction "1_1") (pintype "passive"))
      (node (ref "JP1") (pin "5") (pinfunction "5_5") (pintype "passive"))
      (node (ref "JP10") (pin "3") (pinfunction "3_3") (pintype "passive"))
      (node (ref "JP11") (pin "1") (pinfunction "1_1") (pintype "passive"))
      (node (ref "JP12") (pin "1") (pinfunction "1_1") (pintype "passive"))
      (node (ref "JP13") (pin "1") (pinfunction "1_1") (pintype "passive"))
      (node (ref "JP2") (pin "1") (pinfunction "1_1") (pintype "passive"))
      (node (ref "JP3") (pin "1") (pinfunction "1_1") (pintype "passive"))
      (node (ref "JP3") (pin "5") (pinfunction "5_5") (pintype "passive"))
      (node (ref "JP4") (pin "1") (pinfunction "1_1") (pintype "passive"))
      (node (ref "JP4") (pin "5") (pinfunction "5_5") (pintype "passive"))
      (node (ref "JP5") (pin "1") (pinfunction "1_1") (pintype "passive"))
      (node (ref "JP5") (pin "5") (pinfunction "5_5") (pintype "passive"))
      (node (ref "JP6") (pin "1") (pinfunction "1_1") (pintype "passive"))
      (node (ref "JP6") (pin "5") (pinfunction "5_5") (pintype "passive"))
      (node (ref "JP7") (pin "1") (pinfunction "1_1") (pintype "passive"))
      (node (ref "JP7") (pin "5") (pinfunction "5_5") (pintype "passive"))
      (node (ref "JP8") (pin "1") (pinfunction "1_1") (pintype "passive"))
      (node (ref "JP8") (pin "5") (pinfunction "5_5") (pintype "passive"))
      (node (ref "JP9") (pin "1") (pinfunction "1_1") (pintype "passive"))
      (node (ref "JP9") (pin "5") (pinfunction "5_5") (pintype "passive"))
      (node (ref "Q17") (pin "2") (pinfunction "S_2") (pintype "passive"))
      (node (ref "Q18") (pin "2") (pinfunction "S_2") (pintype "passive"))
      (node (ref "Q19") (pin "2") (pinfunction "S_2") (pintype "passive"))
      (node (ref "Q20") (pin "2") (pinfunction "S_2") (pintype "passive"))
      (node (ref "Q21") (pin "2") (pinfunction "S_2") (pintype "passive"))
      (node (ref "R118") (pin "1") (pinfunction "1_1") (pintype "passive"))
      (node (ref "R119") (pin "1") (pinfunction "1_1") (pintype "passive"))
      (node (ref "R120") (pin "1") (pinfunction "1_1") (pintype "passive"))
      (node (ref "R121") (pin "1") (pinfunction "1_1") (pintype "passive"))
      (node (ref "R2") (pin "1") (pinfunction "1_1") (pintype "passive"))
      (node (ref "R4") (pin "1") (pinfunction "1_1") (pintype "passive"))
      (node (ref "U1") (pin "30") (pinfunction "GND_30") (pintype "bidirectional"))
      (node (ref "U2") (pin "30") (pinfunction "GND_30") (pintype "bidirectional"))
    )
    (net (code "41") (name "HV_ENABLE") (class "Default")
      (node (ref "U2") (pin "15") (pinfunction "HVOUT25_15") (pintype "bidirectional"))
    )
    (net (code "42") (name "HV_IN") (class "Default")
      (node (ref "JP2") (pin "2") (pinfunction "2_2") (pintype "passive"))
      (node (ref "R1") (pin "1") (pinfunction "1_1") (pintype "passive"))
      (node (ref "R3") (pin "1") (pinfunction "1_1") (pintype "passive"))
      (node (ref "R5") (pin "1") (pinfunction "1_1") (pintype "passive"))
    )
    (net (code "43") (name "HV_VBA") (class "Default")
      (node (ref "JP12") (pin "2") (pinfunction "2_2") (pintype "passive"))
      (node (ref "Q1") (pin "2") (pinfunction "S_2") (pintype "passive"))
      (node (ref "Q10") (pin "2") (pinfunction "S_2") (pintype "passive"))
      (node (ref "Q11") (pin "2") (pinfunction "S_2") (pintype "passive"))
      (node (ref "Q12") (pin "2") (pinfunction "S_2") (pintype "passive"))
      (node (ref "Q13") (pin "2") (pinfunction "S_2") (pintype "passive"))
      (node (ref "Q14") (pin "2") (pinfunction "S_2") (pintype "passive"))
      (node (ref "Q15") (pin "2") (pinfunction "S_2") (pintype "passive"))
      (node (ref "Q16") (pin "2") (pinfunction "S_2") (pintype "passive"))
      (node (ref "Q2") (pin "2") (pinfunction "S_2") (pintype "passive"))
      (node (ref "Q3") (pin "2") (pinfunction "S_2") (pintype "passive"))
      (node (ref "Q4") (pin "2") (pinfunction "S_2") (pintype "passive"))
      (node (ref "Q5") (pin "2") (pinfunction "S_2") (pintype "passive"))
      (node (ref "Q6") (pin "2") (pinfunction "S_2") (pintype "passive"))
      (node (ref "Q7") (pin "2") (pinfunction "S_2") (pintype "passive"))
      (node (ref "Q8") (pin "2") (pinfunction "S_2") (pintype "passive"))
      (node (ref "Q9") (pin "2") (pinfunction "S_2") (pintype "passive"))
      (node (ref "R14") (pin "2") (pinfunction "2_2") (pintype "passive"))
      (node (ref "R16") (pin "2") (pinfunction "2_2") (pintype "passive"))
      (node (ref "R18") (pin "2") (pinfunction "2_2") (pintype "passive"))
      (node (ref "R20") (pin "2") (pinfunction "2_2") (pintype "passive"))
      (node (ref "R22") (pin "2") (pinfunction "2_2") (pintype "passive"))
      (node (ref "R24") (pin "2") (pinfunction "2_2") (pintype "passive"))
      (node (ref "R26") (pin "2") (pinfunction "2_2") (pintype "passive"))
      (node (ref "R28") (pin "2") (pinfunction "2_2") (pintype "passive"))
      (node (ref "R30") (pin "2") (pinfunction "2_2") (pintype "passive"))
      (node (ref "R32") (pin "2") (pinfunction "2_2") (pintype "passive"))
      (node (ref "R34") (pin "2") (pinfunction "2_2") (pintype "passive"))
      (node (ref "R36") (pin "2") (pinfunction "2_2") (pintype "passive"))
      (node (ref "R38") (pin "2") (pinfunction "2_2") (pintype "passive"))
      (node (ref "R40") (pin "2") (pinfunction "2_2") (pintype "passive"))
      (node (ref "R42") (pin "2") (pinfunction "2_2") (pintype "passive"))
      (node (ref "R44") (pin "2") (pinfunction "2_2") (pintype "passive"))
      (node (ref "R5") (pin "2") (pinfunction "2_2") (pintype "passive"))
    )
    (net (code "44") (name "HV_VBA_OFF") (class "Default")
      (node (ref "D1") (pin "3") (pinfunction "A_3") (pintype "passive"))
      (node (ref "D2") (pin "3") (pinfunction "A_3") (pintype "passive"))
      (node (ref "D3") (pin "3") (pinfunction "A_3") (pintype "passive"))
      (node (ref "D4") (pin "3") (pinfunction "A_3") (pintype "passive"))
      (node (ref "D5") (pin "3") (pinfunction "A_3") (pintype "passive"))
      (node (ref "D6") (pin "3") (pinfunction "A_3") (pintype "passive"))
      (node (ref "D7") (pin "3") (pinfunction "A_3") (pintype "passive"))
      (node (ref "D8") (pin "3") (pinfunction "A_3") (pintype "passive"))
      (node (ref "JP11") (pin "2") (pinfunction "2_2") (pintype "passive"))
      (node (ref "R3") (pin "2") (pinfunction "2_2") (pintype "passive"))
      (node (ref "R4") (pin "2") (pinfunction "2_2") (pintype "passive"))
    )
    (net (code "45") (name "HV_VS") (class "Default")
      (node (ref "JP13") (pin "2") (pinfunction "2_2") (pintype "passive"))
      (node (ref "R1") (pin "2") (pinfunction "2_2") (pintype "passive"))
      (node (ref "R10") (pin "2") (pinfunction "2_2") (pintype "passive"))
      (node (ref "R11") (pin "2") (pinfunction "2_2") (pintype "passive"))
      (node (ref "R12") (pin "2") (pinfunction "2_2") (pintype "passive"))
      (node (ref "R13") (pin "2") (pinfunction "2_2") (pintype "passive"))
      (node (ref "R2") (pin "2") (pinfunction "2_2") (pintype "passive"))
      (node (ref "R54") (pin "1") (pinfunction "1_1") (pintype "passive"))
      (node (ref "R55") (pin "1") (pinfunction "1_1") (pintype "passive"))
      (node (ref "R56") (pin "1") (pinfunction "1_1") (pintype "passive"))
      (node (ref "R57") (pin "1") (pinfunction "1_1") (pintype "passive"))
      (node (ref "R58") (pin "1") (pinfunction "1_1") (pintype "passive"))
      (node (ref "R59") (pin "1") (pinfunction "1_1") (pintype "passive"))
      (node (ref "R6") (pin "2") (pinfunction "2_2") (pintype "passive"))
      (node (ref "R60") (pin "1") (pinfunction "1_1") (pintype "passive"))
      (node (ref "R61") (pin "1") (pinfunction "1_1") (pintype "passive"))
      (node (ref "R62") (pin "1") (pinfunction "1_1") (pintype "passive"))
      (node (ref "R63") (pin "1") (pinfunction "1_1") (pintype "passive"))
      (node (ref "R64") (pin "1") (pinfunction "1_1") (pintype "passive"))
      (node (ref "R65") (pin "1") (pinfunction "1_1") (pintype "passive"))
      (node (ref "R66") (pin "1") (pinfunction "1_1") (pintype "passive"))
      (node (ref "R67") (pin "1") (pinfunction "1_1") (pintype "passive"))
      (node (ref "R68") (pin "1") (pinfunction "1_1") (pintype "passive"))
      (node (ref "R69") (pin "1") (pinfunction "1_1") (pintype "passive"))
      (node (ref "R7") (pin "2") (pinfunction "2_2") (pintype "passive"))
      (node (ref "R70") (pin "1") (pinfunction "1_1") (pintype "passive"))
      (node (ref "R71") (pin "1") (pinfunction "1_1") (pintype "passive"))
      (node (ref "R72") (pin "1") (pinfunction "1_1") (pintype "passive"))
      (node (ref "R73") (pin "1") (pinfunction "1_1") (pintype "passive"))
      (node (ref "R74") (pin "1") (pinfunction "1_1") (pintype "passive"))
      (node (ref "R75") (pin "1") (pinfunction "1_1") (pintype "passive"))
      (node (ref "R76") (pin "1") (pinfunction "1_1") (pintype "passive"))
      (node (ref "R77") (pin "1") (pinfunction "1_1") (pintype "passive"))
      (node (ref "R78") (pin "1") (pinfunction "1_1") (pintype "passive"))
      (node (ref "R79") (pin "1") (pinfunction "1_1") (pintype "passive"))
      (node (ref "R8") (pin "2") (pinfunction "2_2") (pintype "passive"))
      (node (ref "R80") (pin "1") (pinfunction "1_1") (pintype "passive"))
      (node (ref "R81") (pin "1") (pinfunction "1_1") (pintype "passive"))
      (node (ref "R82") (pin "1") (pinfunction "1_1") (pintype "passive"))
      (node (ref "R83") (pin "1") (pinfunction "1_1") (pintype "passive"))
      (node (ref "R84") (pin "1") (pinfunction "1_1") (pintype "passive"))
      (node (ref "R85") (pin "1") (pinfunction "1_1") (pintype "passive"))
      (node (ref "R86") (pin "1") (pinfunction "1_1") (pintype "passive"))
      (node (ref "R87") (pin "1") (pinfunction "1_1") (pintype "passive"))
      (node (ref "R88") (pin "1") (pinfunction "1_1") (pintype "passive"))
      (node (ref "R89") (pin "1") (pinfunction "1_1") (pintype "passive"))
      (node (ref "R9") (pin "2") (pinfunction "2_2") (pintype "passive"))
      (node (ref "R90") (pin "1") (pinfunction "1_1") (pintype "passive"))
      (node (ref "R91") (pin "1") (pinfunction "1_1") (pintype "passive"))
      (node (ref "R92") (pin "1") (pinfunction "1_1") (pintype "passive"))
      (node (ref "R93") (pin "1") (pinfunction "1_1") (pintype "passive"))
    )
    (net (code "46") (name "K01_DIG1") (class "Default")
      (node (ref "JP1") (pin "6") (pinfunction "6_6") (pintype "passive"))
      (node (ref "R54") (pin "2") (pinfunction "2_2") (pintype "passive"))
      (node (ref "U1") (pin "37") (pinfunction "HVOUT3_37") (pintype "bidirectional"))
    )
    (net (code "47") (name "K01_DIG2") (class "Default")
      (node (ref "JP3") (pin "6") (pinfunction "6_6") (pintype "passive"))
      (node (ref "R59") (pin "2") (pinfunction "2_2") (pintype "passive"))
      (node (ref "U1") (pin "44") (pinfunction "HVOUT10_44") (pintype "bidirectional"))
    )
    (net (code "48") (name "K01_DIG3") (class "Default")
      (node (ref "JP4") (pin "6") (pinfunction "6_6") (pintype "passive"))
      (node (ref "R64") (pin "2") (pinfunction "2_2") (pintype "passive"))
      (node (ref "U1") (pin "7") (pinfunction "HVOUT17_7") (pintype "bidirectional"))
    )
    (net (code "49") (name "K01_DIG4") (class "Default")
      (node (ref "JP5") (pin "6") (pinfunction "6_6") (pintype "passive"))
      (node (ref "R69") (pin "2") (pinfunction "2_2") (pintype "passive"))
      (node (ref "U1") (pin "14") (pinfunction "HVOUT24_14") (pintype "bidirectional"))
    )
    (net (code "50") (name "K01_DIG5") (class "Default")
      (node (ref "JP6") (pin "6") (pinfunction "6_6") (pintype "passive"))
      (node (ref "R74") (pin "2") (pinfunction "2_2") (pintype "passive"))
      (node (ref "U1") (pin "21") (pinfunction "HVOUT31_21") (pintype "bidirectional"))
    )
    (net (code "51") (name "K01_DIG6") (class "Default")
      (node (ref "JP7") (pin "6") (pinfunction "6_6") (pintype "passive"))
      (node (ref "R79") (pin "2") (pinfunction "2_2") (pintype "passive"))
      (node (ref "U2") (pin "40") (pinfunction "HVOUT6_40") (pintype "bidirectional"))
    )
    (net (code "52") (name "K01_DIG7") (class "Default")
      (node (ref "JP8") (pin "6") (pinfunction "6_6") (pintype "passive"))
      (node (ref "R84") (pin "2") (pinfunction "2_2") (pintype "passive"))
      (node (ref "U2") (pin "3") (pinfunction "HVOUT13_3") (pintype "bidirectional"))
    )
    (net (code "53") (name "K01_DIG8") (class "Default")
      (node (ref "JP9") (pin "6") (pinfunction "6_6") (pintype "passive"))
      (node (ref "R89") (pin "2") (pinfunction "2_2") (pintype "passive"))
      (node (ref "U2") (pin "10") (pinfunction "HVOUT20_10") (pintype "bidirectional"))
    )
    (net (code "54") (name "K23_DIG1") (class "Default")
      (node (ref "JP1") (pin "7") (pinfunction "7_7") (pintype "passive"))
      (node (ref "R55") (pin "2") (pinfunction "2_2") (pintype "passive"))
      (node (ref "U1") (pin "38") (pinfunction "HVOUT4_38") (pintype "bidirectional"))
    )
    (net (code "55") (name "K23_DIG2") (class "Default")
      (node (ref "JP3") (pin "7") (pinfunction "7_7") (pintype "passive"))
      (node (ref "R60") (pin "2") (pinfunction "2_2") (pintype "passive"))
      (node (ref "U1") (pin "1") (pinfunction "HVOUT11_1") (pintype "bidirectional"))
    )
    (net (code "56") (name "K23_DIG3") (class "Default")
      (node (ref "JP4") (pin "7") (pinfunction "7_7") (pintype "passive"))
      (node (ref "R65") (pin "2") (pinfunction "2_2") (pintype "passive"))
      (node (ref "U1") (pin "8") (pinfunction "HVOUT18_8") (pintype "bidirectional"))
    )
    (net (code "57") (name "K23_DIG4") (class "Default")
      (node (ref "JP5") (pin "7") (pinfunction "7_7") (pintype "passive"))
      (node (ref "R70") (pin "2") (pinfunction "2_2") (pintype "passive"))
      (node (ref "U1") (pin "15") (pinfunction "HVOUT25_15") (pintype "bidirectional"))
    )
    (net (code "58") (name "K23_DIG5") (class "Default")
      (node (ref "JP6") (pin "7") (pinfunction "7_7") (pintype "passive"))
      (node (ref "R75") (pin "2") (pinfunction "2_2") (pintype "passive"))
      (node (ref "U1") (pin "22") (pinfunction "HVOUT32_22") (pintype "bidirectional"))
    )
    (net (code "59") (name "K23_DIG6") (class "Default")
      (node (ref "JP7") (pin "7") (pinfunction "7_7") (pintype "passive"))
      (node (ref "R80") (pin "2") (pinfunction "2_2") (pintype "passive"))
      (node (ref "U2") (pin "41") (pinfunction "HVOUT7_41") (pintype "bidirectional"))
    )
    (net (code "60") (name "K23_DIG7") (class "Default")
      (node (ref "JP8") (pin "7") (pinfunction "7_7") (pintype "passive"))
      (node (ref "R85") (pin "2") (pinfunction "2_2") (pintype "passive"))
      (node (ref "U2") (pin "4") (pinfunction "HVOUT14_4") (pintype "bidirectional"))
    )
    (net (code "61") (name "K23_DIG8") (class "Default")
      (node (ref "JP9") (pin "7") (pinfunction "7_7") (pintype "passive"))
      (node (ref "R90") (pin "2") (pinfunction "2_2") (pintype "passive"))
      (node (ref "U2") (pin "11") (pinfunction "HVOUT21_11") (pintype "bidirectional"))
    )
    (net (code "62") (name "K45_DIG1") (class "Default")
      (node (ref "JP1") (pin "8") (pinfunction "8_8") (pintype "passive"))
      (node (ref "R56") (pin "2") (pinfunction "2_2") (pintype "passive"))
      (node (ref "U1") (pin "39") (pinfunction "HVOUT5_39") (pintype "bidirectional"))
    )
    (net (code "63") (name "K45_DIG2") (class "Default")
      (node (ref "JP3") (pin "8") (pinfunction "8_8") (pintype "passive"))
      (node (ref "R61") (pin "2") (pinfunction "2_2") (pintype "passive"))
      (node (ref "U1") (pin "2") (pinfunction "HVOUT12_2") (pintype "bidirectional"))
    )
    (net (code "64") (name "K45_DIG3") (class "Default")
      (node (ref "JP4") (pin "8") (pinfunction "8_8") (pintype "passive"))
      (node (ref "R66") (pin "2") (pinfunction "2_2") (pintype "passive"))
      (node (ref "U1") (pin "9") (pinfunction "HVOUT19_9") (pintype "bidirectional"))
    )
    (net (code "65") (name "K45_DIG4") (class "Default")
      (node (ref "JP5") (pin "8") (pinfunction "8_8") (pintype "passive"))
      (node (ref "R71") (pin "2") (pinfunction "2_2") (pintype "passive"))
      (node (ref "U1") (pin "16") (pinfunction "HVOUT26_16") (pintype "bidirectional"))
    )
    (net (code "66") (name "K45_DIG5") (class "Default")
      (node (ref "JP6") (pin "8") (pinfunction "8_8") (pintype "passive"))
      (node (ref "R76") (pin "2") (pinfunction "2_2") (pintype "passive"))
      (node (ref "U2") (pin "35") (pinfunction "HVOUT1_35") (pintype "bidirectional"))
    )
    (net (code "67") (name "K45_DIG6") (class "Default")
      (node (ref "JP7") (pin "8") (pinfunction "8_8") (pintype "passive"))
      (node (ref "R81") (pin "2") (pinfunction "2_2") (pintype "passive"))
      (node (ref "U2") (pin "42") (pinfunction "HVOUT8_42") (pintype "bidirectional"))
    )
    (net (code "68") (name "K45_DIG7") (class "Default")
      (node (ref "JP8") (pin "8") (pinfunction "8_8") (pintype "passive"))
      (node (ref "R86") (pin "2") (pinfunction "2_2") (pintype "passive"))
      (node (ref "U2") (pin "5") (pinfunction "HVOUT15_5") (pintype "bidirectional"))
    )
    (net (code "69") (name "K45_DIG8") (class "Default")
      (node (ref "JP9") (pin "8") (pinfunction "8_8") (pintype "passive"))
      (node (ref "R91") (pin "2") (pinfunction "2_2") (pintype "passive"))
      (node (ref "U2") (pin "12") (pinfunction "HVOUT22_12") (pintype "bidirectional"))
    )
    (net (code "70") (name "K67_DIG1") (class "Default")
      (node (ref "JP1") (pin "9") (pinfunction "9_9") (pintype "passive"))
      (node (ref "R57") (pin "2") (pinfunction "2_2") (pintype "passive"))
      (node (ref "U1") (pin "40") (pinfunction "HVOUT6_40") (pintype "bidirectional"))
    )
    (net (code "71") (name "K67_DIG2") (class "Default")
      (node (ref "JP3") (pin "9") (pinfunction "9_9") (pintype "passive"))
      (node (ref "R62") (pin "2") (pinfunction "2_2") (pintype "passive"))
      (node (ref "U1") (pin "3") (pinfunction "HVOUT13_3") (pintype "bidirectional"))
    )
    (net (code "72") (name "K67_DIG3") (class "Default")
      (node (ref "JP4") (pin "9") (pinfunction "9_9") (pintype "passive"))
      (node (ref "R67") (pin "2") (pinfunction "2_2") (pintype "passive"))
      (node (ref "U1") (pin "10") (pinfunction "HVOUT20_10") (pintype "bidirectional"))
    )
    (net (code "73") (name "K67_DIG4") (class "Default")
      (node (ref "JP5") (pin "9") (pinfunction "9_9") (pintype "passive"))
      (node (ref "R72") (pin "2") (pinfunction "2_2") (pintype "passive"))
      (node (ref "U1") (pin "17") (pinfunction "HVOUT27_17") (pintype "bidirectional"))
    )
    (net (code "74") (name "K67_DIG5") (class "Default")
      (node (ref "JP6") (pin "9") (pinfunction "9_9") (pintype "passive"))
      (node (ref "R77") (pin "2") (pinfunction "2_2") (pintype "passive"))
      (node (ref "U2") (pin "36") (pinfunction "HVOUT2_36") (pintype "bidirectional"))
    )
    (net (code "75") (name "K67_DIG6") (class "Default")
      (node (ref "JP7") (pin "9") (pinfunction "9_9") (pintype "passive"))
      (node (ref "R82") (pin "2") (pinfunction "2_2") (pintype "passive"))
      (node (ref "U2") (pin "43") (pinfunction "HVOUT9_43") (pintype "bidirectional"))
    )
    (net (code "76") (name "K67_DIG7") (class "Default")
      (node (ref "JP8") (pin "9") (pinfunction "9_9") (pintype "passive"))
      (node (ref "R87") (pin "2") (pinfunction "2_2") (pintype "passive"))
      (node (ref "U2") (pin "6") (pinfunction "HVOUT16_6") (pintype "bidirectional"))
    )
    (net (code "77") (name "K67_DIG8") (class "Default")
      (node (ref "JP9") (pin "9") (pinfunction "9_9") (pintype "passive"))
      (node (ref "R92") (pin "2") (pinfunction "2_2") (pintype "passive"))
      (node (ref "U2") (pin "13") (pinfunction "HVOUT23_13") (pintype "bidirectional"))
    )
    (net (code "78") (name "K89_DIG1") (class "Default")
      (node (ref "JP1") (pin "10") (pinfunction "10_10") (pintype "passive"))
      (node (ref "R58") (pin "2") (pinfunction "2_2") (pintype "passive"))
      (node (ref "U1") (pin "41") (pinfunction "HVOUT7_41") (pintype "bidirectional"))
    )
    (net (code "79") (name "K89_DIG2") (class "Default")
      (node (ref "JP3") (pin "10") (pinfunction "10_10") (pintype "passive"))
      (node (ref "R63") (pin "2") (pinfunction "2_2") (pintype "passive"))
      (node (ref "U1") (pin "4") (pinfunction "HVOUT14_4") (pintype "bidirectional"))
    )
    (net (code "80") (name "K89_DIG3") (class "Default")
      (node (ref "JP4") (pin "10") (pinfunction "10_10") (pintype "passive"))
      (node (ref "R68") (pin "2") (pinfunction "2_2") (pintype "passive"))
      (node (ref "U1") (pin "11") (pinfunction "HVOUT21_11") (pintype "bidirectional"))
    )
    (net (code "81") (name "K89_DIG4") (class "Default")
      (node (ref "JP5") (pin "10") (pinfunction "10_10") (pintype "passive"))
      (node (ref "R73") (pin "2") (pinfunction "2_2") (pintype "passive"))
      (node (ref "U1") (pin "18") (pinfunction "HVOUT28_18") (pintype "bidirectional"))
    )
    (net (code "82") (name "K89_DIG5") (class "Default")
      (node (ref "JP6") (pin "10") (pinfunction "10_10") (pintype "passive"))
      (node (ref "R78") (pin "2") (pinfunction "2_2") (pintype "passive"))
      (node (ref "U2") (pin "37") (pinfunction "HVOUT3_37") (pintype "bidirectional"))
    )
    (net (code "83") (name "K89_DIG6") (class "Default")
      (node (ref "JP7") (pin "10") (pinfunction "10_10") (pintype "passive"))
      (node (ref "R83") (pin "2") (pinfunction "2_2") (pintype "passive"))
      (node (ref "U2") (pin "44") (pinfunction "HVOUT10_44") (pintype "bidirectional"))
    )
    (net (code "84") (name "K89_DIG7") (class "Default")
      (node (ref "JP8") (pin "10") (pinfunction "10_10") (pintype "passive"))
      (node (ref "R88") (pin "2") (pinfunction "2_2") (pintype "passive"))
      (node (ref "U2") (pin "7") (pinfunction "HVOUT17_7") (pintype "bidirectional"))
    )
    (net (code "85") (name "K89_DIG8") (class "Default")
      (node (ref "JP9") (pin "10") (pinfunction "10_10") (pintype "passive"))
      (node (ref "R93") (pin "2") (pinfunction "2_2") (pintype "passive"))
      (node (ref "U2") (pin "14") (pinfunction "HVOUT24_14") (pintype "bidirectional"))
    )
    (net (code "86") (name "Net-(D1-K1)") (class "Default")
      (node (ref "D1") (pin "1") (pinfunction "K1_1") (pintype "passive"))
      (node (ref "R46") (pin "2") (pinfunction "2_2") (pintype "passive"))
    )
    (net (code "87") (name "Net-(D1-K2)") (class "Default")
      (node (ref "D1") (pin "2") (pinfunction "K2_2") (pintype "passive"))
      (node (ref "R48") (pin "2") (pinfunction "2_2") (pintype "passive"))
    )
    (net (code "88") (name "Net-(D2-K1)") (class "Default")
      (node (ref "D2") (pin "1") (pinfunction "K1_1") (pintype "passive"))
      (node (ref "R50") (pin "2") (pinfunction "2_2") (pintype "passive"))
    )
    (net (code "89") (name "Net-(D2-K2)") (class "Default")
      (node (ref "D2") (pin "2") (pinfunction "K2_2") (pintype "passive"))
      (node (ref "R52") (pin "2") (pinfunction "2_2") (pintype "passive"))
    )
    (net (code "90") (name "Net-(D3-K1)") (class "Default")
      (node (ref "D3") (pin "1") (pinfunction "K1_1") (pintype "passive"))
      (node (ref "R94") (pin "2") (pinfunction "2_2") (pintype "passive"))
    )
    (net (code "91") (name "Net-(D3-K2)") (class "Default")
      (node (ref "D3") (pin "2") (pinfunction "K2_2") (pintype "passive"))
      (node (ref "R96") (pin "2") (pinfunction "2_2") (pintype "passive"))
    )
    (net (code "92") (name "Net-(D4-K1)") (class "Default")
      (node (ref "D4") (pin "1") (pinfunction "K1_1") (pintype "passive"))
      (node (ref "R98") (pin "2") (pinfunction "2_2") (pintype "passive"))
    )
    (net (code "93") (name "Net-(D4-K2)") (class "Default")
      (node (ref "D4") (pin "2") (pinfunction "K2_2") (pintype "passive"))
      (node (ref "R100") (pin "2") (pinfunction "2_2") (pintype "passive"))
    )
    (net (code "94") (name "Net-(D5-K1)") (class "Default")
      (node (ref "D5") (pin "1") (pinfunction "K1_1") (pintype "passive"))
      (node (ref "R102") (pin "2") (pinfunction "2_2") (pintype "passive"))
    )
    (net (code "95") (name "Net-(D5-K2)") (class "Default")
      (node (ref "D5") (pin "2") (pinfunction "K2_2") (pintype "passive"))
      (node (ref "R104") (pin "2") (pinfunction "2_2") (pintype "passive"))
    )
    (net (code "96") (name "Net-(D6-K1)") (class "Default")
      (node (ref "D6") (pin "1") (pinfunction "K1_1") (pintype "passive"))
      (node (ref "R106") (pin "2") (pinfunction "2_2") (pintype "passive"))
    )
    (net (code "97") (name "Net-(D6-K2)") (class "Default")
      (node (ref "D6") (pin "2") (pinfunction "K2_2") (pintype "passive"))
      (node (ref "R108") (pin "2") (pinfunction "2_2") (pintype "passive"))
    )
    (net (code "98") (name "Net-(D7-K1)") (class "Default")
      (node (ref "D7") (pin "1") (pinfunction "K1_1") (pintype "passive"))
      (node (ref "R110") (pin "2") (pinfunction "2_2") (pintype "passive"))
    )
    (net (code "99") (name "Net-(D7-K2)") (class "Default")
      (node (ref "D7") (pin "2") (pinfunction "K2_2") (pintype "passive"))
      (node (ref "R112") (pin "2") (pinfunction "2_2") (pintype "passive"))
    )
    (net (code "100") (name "Net-(D8-K1)") (class "Default")
      (node (ref "D8") (pin "1") (pinfunction "K1_1") (pintype "passive"))
      (node (ref "R114") (pin "2") (pinfunction "2_2") (pintype "passive"))
    )
    (net (code "101") (name "Net-(D8-K2)") (class "Default")
      (node (ref "D8") (pin "2") (pinfunction "K2_2") (pintype "passive"))
      (node (ref "R116") (pin "2") (pinfunction "2_2") (pintype "passive"))
    )
    (net (code "102") (name "Net-(Q1-D)") (class "Default")
      (node (ref "Q1") (pin "3") (pinfunction "D_3") (pintype "passive"))
      (node (ref "R47") (pin "1") (pinfunction "1_1") (pintype "passive"))
    )
    (net (code "103") (name "Net-(Q1-G)") (class "Default")
      (node (ref "Q1") (pin "1") (pinfunction "G_1") (pintype "passive"))
      (node (ref "R14") (pin "1") (pinfunction "1_1") (pintype "passive"))
      (node (ref "R15") (pin "2") (pinfunction "2_2") (pintype "passive"))
    )
    (net (code "104") (name "Net-(Q2-D)") (class "Default")
      (node (ref "Q2") (pin "3") (pinfunction "D_3") (pintype "passive"))
      (node (ref "R49") (pin "1") (pinfunction "1_1") (pintype "passive"))
    )
    (net (code "105") (name "Net-(Q2-G)") (class "Default")
      (node (ref "Q2") (pin "1") (pinfunction "G_1") (pintype "passive"))
      (node (ref "R16") (pin "1") (pinfunction "1_1") (pintype "passive"))
      (node (ref "R17") (pin "2") (pinfunction "2_2") (pintype "passive"))
    )
    (net (code "106") (name "Net-(Q3-D)") (class "Default")
      (node (ref "Q3") (pin "3") (pinfunction "D_3") (pintype "passive"))
      (node (ref "R51") (pin "1") (pinfunction "1_1") (pintype "passive"))
    )
    (net (code "107") (name "Net-(Q3-G)") (class "Default")
      (node (ref "Q3") (pin "1") (pinfunction "G_1") (pintype "passive"))
      (node (ref "R18") (pin "1") (pinfunction "1_1") (pintype "passive"))
      (node (ref "R19") (pin "2") (pinfunction "2_2") (pintype "passive"))
    )
    (net (code "108") (name "Net-(Q4-D)") (class "Default")
      (node (ref "Q4") (pin "3") (pinfunction "D_3") (pintype "passive"))
      (node (ref "R53") (pin "1") (pinfunction "1_1") (pintype "passive"))
    )
    (net (code "109") (name "Net-(Q4-G)") (class "Default")
      (node (ref "Q4") (pin "1") (pinfunction "G_1") (pintype "passive"))
      (node (ref "R20") (pin "1") (pinfunction "1_1") (pintype "passive"))
      (node (ref "R21") (pin "2") (pinfunction "2_2") (pintype "passive"))
    )
    (net (code "110") (name "Net-(Q5-D)") (class "Default")
      (node (ref "Q5") (pin "3") (pinfunction "D_3") (pintype "passive"))
      (node (ref "R95") (pin "1") (pinfunction "1_1") (pintype "passive"))
    )
    (net (code "111") (name "Net-(Q5-G)") (class "Default")
      (node (ref "Q5") (pin "1") (pinfunction "G_1") (pintype "passive"))
      (node (ref "R22") (pin "1") (pinfunction "1_1") (pintype "passive"))
      (node (ref "R23") (pin "2") (pinfunction "2_2") (pintype "passive"))
    )
    (net (code "112") (name "Net-(Q6-D)") (class "Default")
      (node (ref "Q6") (pin "3") (pinfunction "D_3") (pintype "passive"))
      (node (ref "R97") (pin "1") (pinfunction "1_1") (pintype "passive"))
    )
    (net (code "113") (name "Net-(Q6-G)") (class "Default")
      (node (ref "Q6") (pin "1") (pinfunction "G_1") (pintype "passive"))
      (node (ref "R24") (pin "1") (pinfunction "1_1") (pintype "passive"))
      (node (ref "R25") (pin "2") (pinfunction "2_2") (pintype "passive"))
    )
    (net (code "114") (name "Net-(Q7-D)") (class "Default")
      (node (ref "Q7") (pin "3") (pinfunction "D_3") (pintype "passive"))
      (node (ref "R99") (pin "1") (pinfunction "1_1") (pintype "passive"))
    )
    (net (code "115") (name "Net-(Q7-G)") (class "Default")
      (node (ref "Q7") (pin "1") (pinfunction "G_1") (pintype "passive"))
      (node (ref "R26") (pin "1") (pinfunction "1_1") (pintype "passive"))
      (node (ref "R27") (pin "2") (pinfunction "2_2") (pintype "passive"))
    )
    (net (code "116") (name "Net-(Q8-D)") (class "Default")
      (node (ref "Q8") (pin "3") (pinfunction "D_3") (pintype "passive"))
      (node (ref "R101") (pin "1") (pinfunction "1_1") (pintype "passive"))
    )
    (net (code "117") (name "Net-(Q8-G)") (class "Default")
      (node (ref "Q8") (pin "1") (pinfunction "G_1") (pintype "passive"))
      (node (ref "R28") (pin "1") (pinfunction "1_1") (pintype "passive"))
      (node (ref "R29") (pin "2") (pinfunction "2_2") (pintype "passive"))
    )
    (net (code "118") (name "Net-(Q9-D)") (class "Default")
      (node (ref "Q9") (pin "3") (pinfunction "D_3") (pintype "passive"))
      (node (ref "R103") (pin "1") (pinfunction "1_1") (pintype "passive"))
    )
    (net (code "119") (name "Net-(Q9-G)") (class "Default")
      (node (ref "Q9") (pin "1") (pinfunction "G_1") (pintype "passive"))
      (node (ref "R30") (pin "1") (pinfunction "1_1") (pintype "passive"))
      (node (ref "R31") (pin "2") (pinfunction "2_2") (pintype "passive"))
    )
    (net (code "120") (name "Net-(Q10-D)") (class "Default")
      (node (ref "Q10") (pin "3") (pinfunction "D_3") (pintype "passive"))
      (node (ref "R105") (pin "1") (pinfunction "1_1") (pintype "passive"))
    )
    (net (code "121") (name "Net-(Q10-G)") (class "Default")
      (node (ref "Q10") (pin "1") (pinfunction "G_1") (pintype "passive"))
      (node (ref "R32") (pin "1") (pinfunction "1_1") (pintype "passive"))
      (node (ref "R33") (pin "2") (pinfunction "2_2") (pintype "passive"))
    )
    (net (code "122") (name "Net-(Q11-D)") (class "Default")
      (node (ref "Q11") (pin "3") (pinfunction "D_3") (pintype "passive"))
      (node (ref "R107") (pin "1") (pinfunction "1_1") (pintype "passive"))
    )
    (net (code "123") (name "Net-(Q11-G)") (class "Default")
      (node (ref "Q11") (pin "1") (pinfunction "G_1") (pintype "passive"))
      (node (ref "R34") (pin "1") (pinfunction "1_1") (pintype "passive"))
      (node (ref "R35") (pin "2") (pinfunction "2_2") (pintype "passive"))
    )
    (net (code "124") (name "Net-(Q12-D)") (class "Default")
      (node (ref "Q12") (pin "3") (pinfunction "D_3") (pintype "passive"))
      (node (ref "R109") (pin "1") (pinfunction "1_1") (pintype "passive"))
    )
    (net (code "125") (name "Net-(Q12-G)") (class "Default")
      (node (ref "Q12") (pin "1") (pinfunction "G_1") (pintype "passive"))
      (node (ref "R36") (pin "1") (pinfunction "1_1") (pintype "passive"))
      (node (ref "R37") (pin "2") (pinfunction "2_2") (pintype "passive"))
    )
    (net (code "126") (name "Net-(Q13-D)") (class "Default")
      (node (ref "Q13") (pin "3") (pinfunction "D_3") (pintype "passive"))
      (node (ref "R111") (pin "1") (pinfunction "1_1") (pintype "passive"))
    )
    (net (code "127") (name "Net-(Q13-G)") (class "Default")
      (node (ref "Q13") (pin "1") (pinfunction "G_1") (pintype "passive"))
      (node (ref "R38") (pin "1") (pinfunction "1_1") (pintype "passive"))
      (node (ref "R39") (pin "2") (pinfunction "2_2") (pintype "passive"))
    )
    (net (code "128") (name "Net-(Q14-D)") (class "Default")
      (node (ref "Q14") (pin "3") (pinfunction "D_3") (pintype "passive"))
      (node (ref "R113") (pin "1") (pinfunction "1_1") (pintype "passive"))
    )
    (net (code "129") (name "Net-(Q14-G)") (class "Default")
      (node (ref "Q14") (pin "1") (pinfunction "G_1") (pintype "passive"))
      (node (ref "R40") (pin "1") (pinfunction "1_1") (pintype "passive"))
      (node (ref "R41") (pin "2") (pinfunction "2_2") (pintype "passive"))
    )
    (net (code "130") (name "Net-(Q15-D)") (class "Default")
      (node (ref "Q15") (pin "3") (pinfunction "D_3") (pintype "passive"))
      (node (ref "R115") (pin "1") (pinfunction "1_1") (pintype "passive"))
    )
    (net (code "131") (name "Net-(Q15-G)") (class "Default")
      (node (ref "Q15") (pin "1") (pinfunction "G_1") (pintype "passive"))
      (node (ref "R42") (pin "1") (pinfunction "1_1") (pintype "passive"))
      (node (ref "R43") (pin "2") (pinfunction "2_2") (pintype "passive"))
    )
    (net (code "132") (name "Net-(Q16-D)") (class "Default")
      (node (ref "Q16") (pin "3") (pinfunction "D_3") (pintype "passive"))
      (node (ref "R117") (pin "1") (pinfunction "1_1") (pintype "passive"))
    )
    (net (code "133") (name "Net-(Q16-G)") (class "Default")
      (node (ref "Q16") (pin "1") (pinfunction "G_1") (pintype "passive"))
      (node (ref "R44") (pin "1") (pinfunction "1_1") (pintype "passive"))
      (node (ref "R45") (pin "2") (pinfunction "2_2") (pintype "passive"))
    )
    (net (code "134") (name "OE") (class "Default")
      (node (ref "JP10") (pin "5") (pinfunction "5_5") (pintype "passive"))
      (node (ref "Q19") (pin "1") (pinfunction "G_1") (pintype "passive"))
      (node (ref "R120") (pin "2") (pinfunction "2_2") (pintype "passive"))
    )
    (net (code "135") (name "OE_HV") (class "Default")
      (node (ref "Q19") (pin "3") (pinfunction "D_3") (pintype "passive"))
      (node (ref "R124") (pin "2") (pinfunction "2_2") (pintype "passive"))
      (node (ref "U1") (pin "28") (pinfunction "OE_28") (pintype "bidirectional"))
      (node (ref "U2") (pin "28") (pinfunction "OE_28") (pintype "bidirectional"))
    )
    (net (code "136") (name "SPARE1") (class "Default")
      (node (ref "JP14") (pin "1") (pinfunction "1_1") (pintype "passive"))
      (node (ref "U2") (pin "16") (pinfunction "HVOUT26_16") (pintype "bidirectional"))
    )
    (net (code "137") (name "SPARE2") (class "Default")
      (node (ref "JP14") (pin "2") (pinfunction "2_2") (pintype "passive"))
      (node (ref "U2") (pin "17") (pinfunction "HVOUT27_17") (pintype "bidirectional"))
    )
    (net (code "138") (name "SPARE3") (class "Default")
      (node (ref "JP14") (pin "3") (pinfunction "3_3") (pintype "passive"))
      (node (ref "U2") (pin "18") (pinfunction "HVOUT28_18") (pintype "bidirectional"))
    )
    (net (code "139") (name "SPARE4") (class "Default")
      (node (ref "JP14") (pin "4") (pinfunction "4_4") (pintype "passive"))
      (node (ref "U2") (pin "19") (pinfunction "HVOUT29_19") (pintype "bidirectional"))
    )
    (net (code "140") (name "SPARE5") (class "Default")
      (node (ref "JP14") (pin "5") (pinfunction "5_5") (pintype "passive"))
      (node (ref "U2") (pin "20") (pinfunction "HVOUT30_20") (pintype "bidirectional"))
    )
    (net (code "141") (name "SPARE6") (class "Default")
      (node (ref "JP14") (pin "6") (pinfunction "6_6") (pintype "passive"))
      (node (ref "U2") (pin "21") (pinfunction "HVOUT31_21") (pintype "bidirectional"))
    )
    (net (code "142") (name "SPARE7") (class "Default")
      (node (ref "JP14") (pin "7") (pinfunction "7_7") (pintype "passive"))
      (node (ref "U2") (pin "22") (pinfunction "HVOUT32_22") (pintype "bidirectional"))
    )
    (net (code "143") (name "STR") (class "Default")
      (node (ref "JP10") (pin "4") (pinfunction "4_4") (pintype "passive"))
      (node (ref "Q20") (pin "1") (pinfunction "G_1") (pintype "passive"))
      (node (ref "R121") (pin "2") (pinfunction "2_2") (pintype "passive"))
    )
    (net (code "144") (name "STR_HV") (class "Default")
      (node (ref "Q20") (pin "3") (pinfunction "D_3") (pintype "passive"))
      (node (ref "R125") (pin "2") (pinfunction "2_2") (pintype "passive"))
      (node (ref "U1") (pin "32") (pinfunction "STR_32") (pintype "bidirectional"))
      (node (ref "U2") (pin "32") (pinfunction "STR_32") (pintype "bidirectional"))
    )
    (net (code "145") (name "S_DIG1") (class "Default")
      (node (ref "JP1") (pin "4") (pinfunction "4_4") (pintype "passive"))
      (node (ref "R6") (pin "1") (pinfunction "1_1") (pintype "passive"))
    )
    (net (code "146") (name "S_DIG2") (class "Default")
      (node (ref "JP3") (pin "4") (pinfunction "4_4") (pintype "passive"))
      (node (ref "R7") (pin "1") (pinfunction "1_1") (pintype "passive"))
    )
    (net (code "147") (name "S_DIG3") (class "Default")
      (node (ref "JP4") (pin "4") (pinfunction "4_4") (pintype "passive"))
      (node (ref "R8") (pin "1") (pinfunction "1_1") (pintype "passive"))
    )
    (net (code "148") (name "S_DIG4") (class "Default")
      (node (ref "JP5") (pin "4") (pinfunction "4_4") (pintype "passive"))
      (node (ref "R9") (pin "1") (pinfunction "1_1") (pintype "passive"))
    )
    (net (code "149") (name "S_DIG5") (class "Default")
      (node (ref "JP6") (pin "4") (pinfunction "4_4") (pintype "passive"))
      (node (ref "R10") (pin "1") (pinfunction "1_1") (pintype "passive"))
    )
    (net (code "150") (name "S_DIG6") (class "Default")
      (node (ref "JP7") (pin "4") (pinfunction "4_4") (pintype "passive"))
      (node (ref "R11") (pin "1") (pinfunction "1_1") (pintype "passive"))
    )
    (net (code "151") (name "S_DIG7") (class "Default")
      (node (ref "JP8") (pin "4") (pinfunction "4_4") (pintype "passive"))
      (node (ref "R12") (pin "1") (pinfunction "1_1") (pintype "passive"))
    )
    (net (code "152") (name "S_DIG8") (class "Default")
      (node (ref "JP9") (pin "4") (pinfunction "4_4") (pintype "passive"))
      (node (ref "R13") (pin "1") (pinfunction "1_1") (pintype "passive"))
    )
    (net (code "153") (name "VCC") (class "Default")
      (node (ref "C1") (pin "1") (pinfunction "1_1") (pintype "passive"))
      (node (ref "C2") (pin "1") (pinfunction "1_1") (pintype "passive"))
      (node (ref "C3") (pin "1") (pinfunction "1_1") (pintype "passive"))
      (node (ref "C4") (pin "1") (pinfunction "1_1") (pintype "passive"))
      (node (ref "JP10") (pin "2") (pinfunction "2_2") (pintype "passive"))
      (node (ref "R122") (pin "1") (pinfunction "1_1") (pintype "passive"))
      (node (ref "R123") (pin "1") (pinfunction "1_1") (pintype "passive"))
      (node (ref "R124") (pin "1") (pinfunction "1_1") (pintype "passive"))
      (node (ref "R125") (pin "1") (pinfunction "1_1") (pintype "passive"))
      (node (ref "U1") (pin "31") (pinfunction "VDD_31") (pintype "bidirectional"))
      (node (ref "U2") (pin "31") (pinfunction "VDD_31") (pintype "bidirectional"))
    )
    (net (code "154") (name "VDD") (class "Default")
      (node (ref "JP10") (pin "1") (pinfunction "1_1") (pintype "passive"))
      (node (ref "R126") (pin "1") (pinfunction "1_1") (pintype "passive"))
    )
    (net (code "155") (name "unconnected-(JP14-Pad8)") (class "Default")
      (node (ref "JP14") (pin "8") (pinfunction "8_8") (pintype "passive"))
    )
  )
)
